# Spannungsteiler_low.net
KiCad netlist of a schematic drawn in Altium Designer
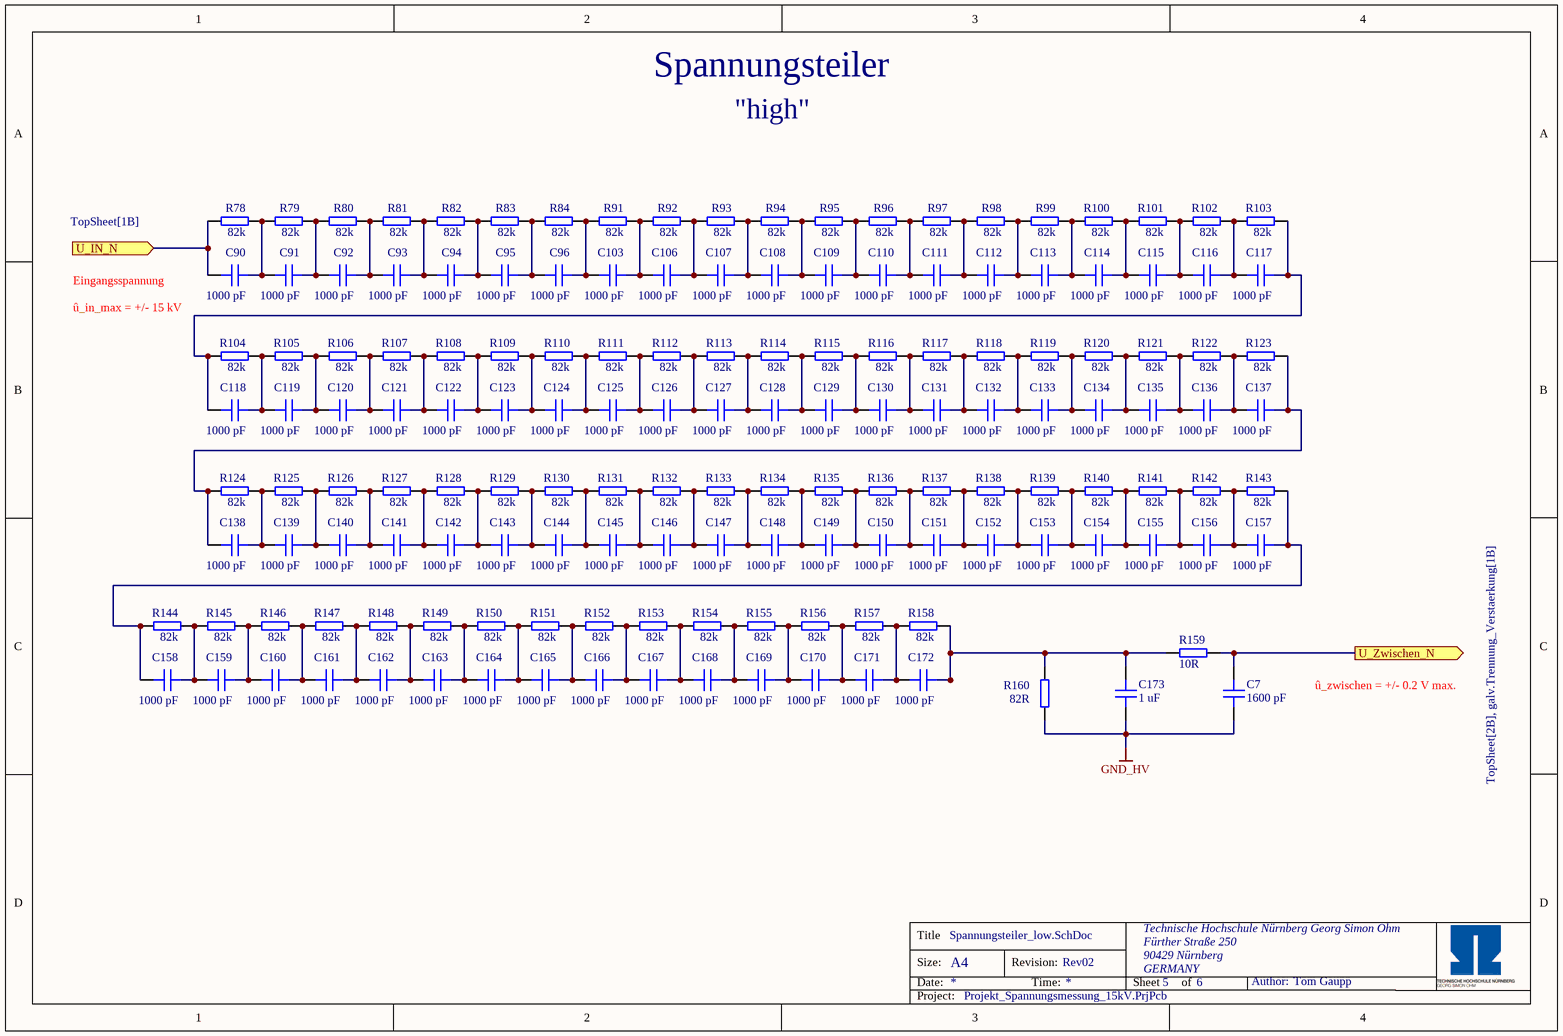
[diagram p0: Spannungsteiler_low.SchDoc]

(export (version "E")
  (design (tool "Eeschema 10.0.6"))
  (components
    (comp (ref "C7")
      (value "1600 pF")
      (footprint "C_1206")
      (description "Capacitor 1206, 25V, 1600pF, X8R, 10%")
      (fields
        (field (name "MANUFACTURER PART NUMBER") "C1206C162K3HACTU")
        (field (name "MANUFACTURER") "KEMET")
        (field (name "CREATED FROM") "TGaupp")
      )
      (libsource (lib "user") (part "Capacitor"))
    )
    (comp (ref "C90")
      (value "1000 pF")
      (footprint "C_1206")
      (description "Capacitor 1206, 200VDC, 1000pF, C0G, 5%")
      (fields
        (field (name "MANUFACTURER") "KEMET")
        (field (name "MANUFACTURER PART NUMBER") "C1206C102J2GACTU")
        (field (name "CREATED FROM") "TGaupp")
      )
      (libsource (lib "user") (part "Capacitor"))
    )
    (comp (ref "C91")
      (value "1000 pF")
      (footprint "C_1206")
      (description "Capacitor 1206, 200VDC, 1000pF, C0G, 5%")
      (fields
        (field (name "MANUFACTURER") "KEMET")
        (field (name "MANUFACTURER PART NUMBER") "C1206C102J2GACTU")
        (field (name "CREATED FROM") "TGaupp")
      )
      (libsource (lib "user") (part "Capacitor"))
    )
    (comp (ref "C92")
      (value "1000 pF")
      (footprint "C_1206")
      (description "Capacitor 1206, 200VDC, 1000pF, C0G, 5%")
      (fields
        (field (name "MANUFACTURER") "KEMET")
        (field (name "MANUFACTURER PART NUMBER") "C1206C102J2GACTU")
        (field (name "CREATED FROM") "TGaupp")
      )
      (libsource (lib "user") (part "Capacitor"))
    )
    (comp (ref "C93")
      (value "1000 pF")
      (footprint "C_1206")
      (description "Capacitor 1206, 200VDC, 1000pF, C0G, 5%")
      (fields
        (field (name "MANUFACTURER") "KEMET")
        (field (name "MANUFACTURER PART NUMBER") "C1206C102J2GACTU")
        (field (name "CREATED FROM") "TGaupp")
      )
      (libsource (lib "user") (part "Capacitor"))
    )
    (comp (ref "C94")
      (value "1000 pF")
      (footprint "C_1206")
      (description "Capacitor 1206, 200VDC, 1000pF, C0G, 5%")
      (fields
        (field (name "MANUFACTURER") "KEMET")
        (field (name "MANUFACTURER PART NUMBER") "C1206C102J2GACTU")
        (field (name "CREATED FROM") "TGaupp")
      )
      (libsource (lib "user") (part "Capacitor"))
    )
    (comp (ref "C95")
      (value "1000 pF")
      (footprint "C_1206")
      (description "Capacitor 1206, 200VDC, 1000pF, C0G, 5%")
      (fields
        (field (name "MANUFACTURER") "KEMET")
        (field (name "MANUFACTURER PART NUMBER") "C1206C102J2GACTU")
        (field (name "CREATED FROM") "TGaupp")
      )
      (libsource (lib "user") (part "Capacitor"))
    )
    (comp (ref "C96")
      (value "1000 pF")
      (footprint "C_1206")
      (description "Capacitor 1206, 200VDC, 1000pF, C0G, 5%")
      (fields
        (field (name "MANUFACTURER") "KEMET")
        (field (name "MANUFACTURER PART NUMBER") "C1206C102J2GACTU")
        (field (name "CREATED FROM") "TGaupp")
      )
      (libsource (lib "user") (part "Capacitor"))
    )
    (comp (ref "C103")
      (value "1000 pF")
      (footprint "C_1206")
      (description "Capacitor 1206, 200VDC, 1000pF, C0G, 5%")
      (fields
        (field (name "MANUFACTURER") "KEMET")
        (field (name "MANUFACTURER PART NUMBER") "C1206C102J2GACTU")
        (field (name "CREATED FROM") "TGaupp")
      )
      (libsource (lib "user") (part "Capacitor"))
    )
    (comp (ref "C106")
      (value "1000 pF")
      (footprint "C_1206")
      (description "Capacitor 1206, 200VDC, 1000pF, C0G, 5%")
      (fields
        (field (name "MANUFACTURER") "KEMET")
        (field (name "MANUFACTURER PART NUMBER") "C1206C102J2GACTU")
        (field (name "CREATED FROM") "TGaupp")
      )
      (libsource (lib "user") (part "Capacitor"))
    )
    (comp (ref "C107")
      (value "1000 pF")
      (footprint "C_1206")
      (description "Capacitor 1206, 200VDC, 1000pF, C0G, 5%")
      (fields
        (field (name "MANUFACTURER") "KEMET")
        (field (name "MANUFACTURER PART NUMBER") "C1206C102J2GACTU")
        (field (name "CREATED FROM") "TGaupp")
      )
      (libsource (lib "user") (part "Capacitor"))
    )
    (comp (ref "C108")
      (value "1000 pF")
      (footprint "C_1206")
      (description "Capacitor 1206, 200VDC, 1000pF, C0G, 5%")
      (fields
        (field (name "MANUFACTURER") "KEMET")
        (field (name "MANUFACTURER PART NUMBER") "C1206C102J2GACTU")
        (field (name "CREATED FROM") "TGaupp")
      )
      (libsource (lib "user") (part "Capacitor"))
    )
    (comp (ref "C109")
      (value "1000 pF")
      (footprint "C_1206")
      (description "Capacitor 1206, 200VDC, 1000pF, C0G, 5%")
      (fields
        (field (name "MANUFACTURER") "KEMET")
        (field (name "MANUFACTURER PART NUMBER") "C1206C102J2GACTU")
        (field (name "CREATED FROM") "TGaupp")
      )
      (libsource (lib "user") (part "Capacitor"))
    )
    (comp (ref "C110")
      (value "1000 pF")
      (footprint "C_1206")
      (description "Capacitor 1206, 200VDC, 1000pF, C0G, 5%")
      (fields
        (field (name "MANUFACTURER") "KEMET")
        (field (name "MANUFACTURER PART NUMBER") "C1206C102J2GACTU")
        (field (name "CREATED FROM") "TGaupp")
      )
      (libsource (lib "user") (part "Capacitor"))
    )
    (comp (ref "C111")
      (value "1000 pF")
      (footprint "C_1206")
      (description "Capacitor 1206, 200VDC, 1000pF, C0G, 5%")
      (fields
        (field (name "MANUFACTURER") "KEMET")
        (field (name "MANUFACTURER PART NUMBER") "C1206C102J2GACTU")
        (field (name "CREATED FROM") "TGaupp")
      )
      (libsource (lib "user") (part "Capacitor"))
    )
    (comp (ref "C112")
      (value "1000 pF")
      (footprint "C_1206")
      (description "Capacitor 1206, 200VDC, 1000pF, C0G, 5%")
      (fields
        (field (name "MANUFACTURER") "KEMET")
        (field (name "MANUFACTURER PART NUMBER") "C1206C102J2GACTU")
        (field (name "CREATED FROM") "TGaupp")
      )
      (libsource (lib "user") (part "Capacitor"))
    )
    (comp (ref "C113")
      (value "1000 pF")
      (footprint "C_1206")
      (description "Capacitor 1206, 200VDC, 1000pF, C0G, 5%")
      (fields
        (field (name "MANUFACTURER") "KEMET")
        (field (name "MANUFACTURER PART NUMBER") "C1206C102J2GACTU")
        (field (name "CREATED FROM") "TGaupp")
      )
      (libsource (lib "user") (part "Capacitor"))
    )
    (comp (ref "C114")
      (value "1000 pF")
      (footprint "C_1206")
      (description "Capacitor 1206, 200VDC, 1000pF, C0G, 5%")
      (fields
        (field (name "MANUFACTURER") "KEMET")
        (field (name "MANUFACTURER PART NUMBER") "C1206C102J2GACTU")
        (field (name "CREATED FROM") "TGaupp")
      )
      (libsource (lib "user") (part "Capacitor"))
    )
    (comp (ref "C115")
      (value "1000 pF")
      (footprint "C_1206")
      (description "Capacitor 1206, 200VDC, 1000pF, C0G, 5%")
      (fields
        (field (name "MANUFACTURER") "KEMET")
        (field (name "MANUFACTURER PART NUMBER") "C1206C102J2GACTU")
        (field (name "CREATED FROM") "TGaupp")
      )
      (libsource (lib "user") (part "Capacitor"))
    )
    (comp (ref "C116")
      (value "1000 pF")
      (footprint "C_1206")
      (description "Capacitor 1206, 200VDC, 1000pF, C0G, 5%")
      (fields
        (field (name "MANUFACTURER") "KEMET")
        (field (name "MANUFACTURER PART NUMBER") "C1206C102J2GACTU")
        (field (name "CREATED FROM") "TGaupp")
      )
      (libsource (lib "user") (part "Capacitor"))
    )
    (comp (ref "C117")
      (value "1000 pF")
      (footprint "C_1206")
      (description "Capacitor 1206, 200VDC, 1000pF, C0G, 5%")
      (fields
        (field (name "MANUFACTURER") "KEMET")
        (field (name "MANUFACTURER PART NUMBER") "C1206C102J2GACTU")
        (field (name "CREATED FROM") "TGaupp")
      )
      (libsource (lib "user") (part "Capacitor"))
    )
    (comp (ref "C118")
      (value "1000 pF")
      (footprint "C_1206")
      (description "Capacitor 1206, 200VDC, 1000pF, C0G, 5%")
      (fields
        (field (name "MANUFACTURER") "KEMET")
        (field (name "MANUFACTURER PART NUMBER") "C1206C102J2GACTU")
        (field (name "CREATED FROM") "TGaupp")
      )
      (libsource (lib "user") (part "Capacitor"))
    )
    (comp (ref "C119")
      (value "1000 pF")
      (footprint "C_1206")
      (description "Capacitor 1206, 200VDC, 1000pF, C0G, 5%")
      (fields
        (field (name "MANUFACTURER") "KEMET")
        (field (name "MANUFACTURER PART NUMBER") "C1206C102J2GACTU")
        (field (name "CREATED FROM") "TGaupp")
      )
      (libsource (lib "user") (part "Capacitor"))
    )
    (comp (ref "C120")
      (value "1000 pF")
      (footprint "C_1206")
      (description "Capacitor 1206, 200VDC, 1000pF, C0G, 5%")
      (fields
        (field (name "MANUFACTURER") "KEMET")
        (field (name "MANUFACTURER PART NUMBER") "C1206C102J2GACTU")
        (field (name "CREATED FROM") "TGaupp")
      )
      (libsource (lib "user") (part "Capacitor"))
    )
    (comp (ref "C121")
      (value "1000 pF")
      (footprint "C_1206")
      (description "Capacitor 1206, 200VDC, 1000pF, C0G, 5%")
      (fields
        (field (name "MANUFACTURER") "KEMET")
        (field (name "MANUFACTURER PART NUMBER") "C1206C102J2GACTU")
        (field (name "CREATED FROM") "TGaupp")
      )
      (libsource (lib "user") (part "Capacitor"))
    )
    (comp (ref "C122")
      (value "1000 pF")
      (footprint "C_1206")
      (description "Capacitor 1206, 200VDC, 1000pF, C0G, 5%")
      (fields
        (field (name "MANUFACTURER") "KEMET")
        (field (name "MANUFACTURER PART NUMBER") "C1206C102J2GACTU")
        (field (name "CREATED FROM") "TGaupp")
      )
      (libsource (lib "user") (part "Capacitor"))
    )
    (comp (ref "C123")
      (value "1000 pF")
      (footprint "C_1206")
      (description "Capacitor 1206, 200VDC, 1000pF, C0G, 5%")
      (fields
        (field (name "MANUFACTURER") "KEMET")
        (field (name "MANUFACTURER PART NUMBER") "C1206C102J2GACTU")
        (field (name "CREATED FROM") "TGaupp")
      )
      (libsource (lib "user") (part "Capacitor"))
    )
    (comp (ref "C124")
      (value "1000 pF")
      (footprint "C_1206")
      (description "Capacitor 1206, 200VDC, 1000pF, C0G, 5%")
      (fields
        (field (name "MANUFACTURER") "KEMET")
        (field (name "MANUFACTURER PART NUMBER") "C1206C102J2GACTU")
        (field (name "CREATED FROM") "TGaupp")
      )
      (libsource (lib "user") (part "Capacitor"))
    )
    (comp (ref "C125")
      (value "1000 pF")
      (footprint "C_1206")
      (description "Capacitor 1206, 200VDC, 1000pF, C0G, 5%")
      (fields
        (field (name "MANUFACTURER") "KEMET")
        (field (name "MANUFACTURER PART NUMBER") "C1206C102J2GACTU")
        (field (name "CREATED FROM") "TGaupp")
      )
      (libsource (lib "user") (part "Capacitor"))
    )
    (comp (ref "C126")
      (value "1000 pF")
      (footprint "C_1206")
      (description "Capacitor 1206, 200VDC, 1000pF, C0G, 5%")
      (fields
        (field (name "MANUFACTURER") "KEMET")
        (field (name "MANUFACTURER PART NUMBER") "C1206C102J2GACTU")
        (field (name "CREATED FROM") "TGaupp")
      )
      (libsource (lib "user") (part "Capacitor"))
    )
    (comp (ref "C127")
      (value "1000 pF")
      (footprint "C_1206")
      (description "Capacitor 1206, 200VDC, 1000pF, C0G, 5%")
      (fields
        (field (name "MANUFACTURER") "KEMET")
        (field (name "MANUFACTURER PART NUMBER") "C1206C102J2GACTU")
        (field (name "CREATED FROM") "TGaupp")
      )
      (libsource (lib "user") (part "Capacitor"))
    )
    (comp (ref "C128")
      (value "1000 pF")
      (footprint "C_1206")
      (description "Capacitor 1206, 200VDC, 1000pF, C0G, 5%")
      (fields
        (field (name "MANUFACTURER") "KEMET")
        (field (name "MANUFACTURER PART NUMBER") "C1206C102J2GACTU")
        (field (name "CREATED FROM") "TGaupp")
      )
      (libsource (lib "user") (part "Capacitor"))
    )
    (comp (ref "C129")
      (value "1000 pF")
      (footprint "C_1206")
      (description "Capacitor 1206, 200VDC, 1000pF, C0G, 5%")
      (fields
        (field (name "MANUFACTURER") "KEMET")
        (field (name "MANUFACTURER PART NUMBER") "C1206C102J2GACTU")
        (field (name "CREATED FROM") "TGaupp")
      )
      (libsource (lib "user") (part "Capacitor"))
    )
    (comp (ref "C130")
      (value "1000 pF")
      (footprint "C_1206")
      (description "Capacitor 1206, 200VDC, 1000pF, C0G, 5%")
      (fields
        (field (name "MANUFACTURER") "KEMET")
        (field (name "MANUFACTURER PART NUMBER") "C1206C102J2GACTU")
        (field (name "CREATED FROM") "TGaupp")
      )
      (libsource (lib "user") (part "Capacitor"))
    )
    (comp (ref "C131")
      (value "1000 pF")
      (footprint "C_1206")
      (description "Capacitor 1206, 200VDC, 1000pF, C0G, 5%")
      (fields
        (field (name "MANUFACTURER") "KEMET")
        (field (name "MANUFACTURER PART NUMBER") "C1206C102J2GACTU")
        (field (name "CREATED FROM") "TGaupp")
      )
      (libsource (lib "user") (part "Capacitor"))
    )
    (comp (ref "C132")
      (value "1000 pF")
      (footprint "C_1206")
      (description "Capacitor 1206, 200VDC, 1000pF, C0G, 5%")
      (fields
        (field (name "MANUFACTURER") "KEMET")
        (field (name "MANUFACTURER PART NUMBER") "C1206C102J2GACTU")
        (field (name "CREATED FROM") "TGaupp")
      )
      (libsource (lib "user") (part "Capacitor"))
    )
    (comp (ref "C133")
      (value "1000 pF")
      (footprint "C_1206")
      (description "Capacitor 1206, 200VDC, 1000pF, C0G, 5%")
      (fields
        (field (name "MANUFACTURER") "KEMET")
        (field (name "MANUFACTURER PART NUMBER") "C1206C102J2GACTU")
        (field (name "CREATED FROM") "TGaupp")
      )
      (libsource (lib "user") (part "Capacitor"))
    )
    (comp (ref "C134")
      (value "1000 pF")
      (footprint "C_1206")
      (description "Capacitor 1206, 200VDC, 1000pF, C0G, 5%")
      (fields
        (field (name "MANUFACTURER") "KEMET")
        (field (name "MANUFACTURER PART NUMBER") "C1206C102J2GACTU")
        (field (name "CREATED FROM") "TGaupp")
      )
      (libsource (lib "user") (part "Capacitor"))
    )
    (comp (ref "C135")
      (value "1000 pF")
      (footprint "C_1206")
      (description "Capacitor 1206, 200VDC, 1000pF, C0G, 5%")
      (fields
        (field (name "MANUFACTURER") "KEMET")
        (field (name "MANUFACTURER PART NUMBER") "C1206C102J2GACTU")
        (field (name "CREATED FROM") "TGaupp")
      )
      (libsource (lib "user") (part "Capacitor"))
    )
    (comp (ref "C136")
      (value "1000 pF")
      (footprint "C_1206")
      (description "Capacitor 1206, 200VDC, 1000pF, C0G, 5%")
      (fields
        (field (name "MANUFACTURER") "KEMET")
        (field (name "MANUFACTURER PART NUMBER") "C1206C102J2GACTU")
        (field (name "CREATED FROM") "TGaupp")
      )
      (libsource (lib "user") (part "Capacitor"))
    )
    (comp (ref "C137")
      (value "1000 pF")
      (footprint "C_1206")
      (description "Capacitor 1206, 200VDC, 1000pF, C0G, 5%")
      (fields
        (field (name "MANUFACTURER") "KEMET")
        (field (name "MANUFACTURER PART NUMBER") "C1206C102J2GACTU")
        (field (name "CREATED FROM") "TGaupp")
      )
      (libsource (lib "user") (part "Capacitor"))
    )
    (comp (ref "C138")
      (value "1000 pF")
      (footprint "C_1206")
      (description "Capacitor 1206, 200VDC, 1000pF, C0G, 5%")
      (fields
        (field (name "MANUFACTURER") "KEMET")
        (field (name "MANUFACTURER PART NUMBER") "C1206C102J2GACTU")
        (field (name "CREATED FROM") "TGaupp")
      )
      (libsource (lib "user") (part "Capacitor"))
    )
    (comp (ref "C139")
      (value "1000 pF")
      (footprint "C_1206")
      (description "Capacitor 1206, 200VDC, 1000pF, C0G, 5%")
      (fields
        (field (name "MANUFACTURER") "KEMET")
        (field (name "MANUFACTURER PART NUMBER") "C1206C102J2GACTU")
        (field (name "CREATED FROM") "TGaupp")
      )
      (libsource (lib "user") (part "Capacitor"))
    )
    (comp (ref "C140")
      (value "1000 pF")
      (footprint "C_1206")
      (description "Capacitor 1206, 200VDC, 1000pF, C0G, 5%")
      (fields
        (field (name "MANUFACTURER") "KEMET")
        (field (name "MANUFACTURER PART NUMBER") "C1206C102J2GACTU")
        (field (name "CREATED FROM") "TGaupp")
      )
      (libsource (lib "user") (part "Capacitor"))
    )
    (comp (ref "C141")
      (value "1000 pF")
      (footprint "C_1206")
      (description "Capacitor 1206, 200VDC, 1000pF, C0G, 5%")
      (fields
        (field (name "MANUFACTURER") "KEMET")
        (field (name "MANUFACTURER PART NUMBER") "C1206C102J2GACTU")
        (field (name "CREATED FROM") "TGaupp")
      )
      (libsource (lib "user") (part "Capacitor"))
    )
    (comp (ref "C142")
      (value "1000 pF")
      (footprint "C_1206")
      (description "Capacitor 1206, 200VDC, 1000pF, C0G, 5%")
      (fields
        (field (name "MANUFACTURER") "KEMET")
        (field (name "MANUFACTURER PART NUMBER") "C1206C102J2GACTU")
        (field (name "CREATED FROM") "TGaupp")
      )
      (libsource (lib "user") (part "Capacitor"))
    )
    (comp (ref "C143")
      (value "1000 pF")
      (footprint "C_1206")
      (description "Capacitor 1206, 200VDC, 1000pF, C0G, 5%")
      (fields
        (field (name "MANUFACTURER") "KEMET")
        (field (name "MANUFACTURER PART NUMBER") "C1206C102J2GACTU")
        (field (name "CREATED FROM") "TGaupp")
      )
      (libsource (lib "user") (part "Capacitor"))
    )
    (comp (ref "C144")
      (value "1000 pF")
      (footprint "C_1206")
      (description "Capacitor 1206, 200VDC, 1000pF, C0G, 5%")
      (fields
        (field (name "MANUFACTURER") "KEMET")
        (field (name "MANUFACTURER PART NUMBER") "C1206C102J2GACTU")
        (field (name "CREATED FROM") "TGaupp")
      )
      (libsource (lib "user") (part "Capacitor"))
    )
    (comp (ref "C145")
      (value "1000 pF")
      (footprint "C_1206")
      (description "Capacitor 1206, 200VDC, 1000pF, C0G, 5%")
      (fields
        (field (name "MANUFACTURER") "KEMET")
        (field (name "MANUFACTURER PART NUMBER") "C1206C102J2GACTU")
        (field (name "CREATED FROM") "TGaupp")
      )
      (libsource (lib "user") (part "Capacitor"))
    )
    (comp (ref "C146")
      (value "1000 pF")
      (footprint "C_1206")
      (description "Capacitor 1206, 200VDC, 1000pF, C0G, 5%")
      (fields
        (field (name "MANUFACTURER") "KEMET")
        (field (name "MANUFACTURER PART NUMBER") "C1206C102J2GACTU")
        (field (name "CREATED FROM") "TGaupp")
      )
      (libsource (lib "user") (part "Capacitor"))
    )
    (comp (ref "C147")
      (value "1000 pF")
      (footprint "C_1206")
      (description "Capacitor 1206, 200VDC, 1000pF, C0G, 5%")
      (fields
        (field (name "MANUFACTURER") "KEMET")
        (field (name "MANUFACTURER PART NUMBER") "C1206C102J2GACTU")
        (field (name "CREATED FROM") "TGaupp")
      )
      (libsource (lib "user") (part "Capacitor"))
    )
    (comp (ref "C148")
      (value "1000 pF")
      (footprint "C_1206")
      (description "Capacitor 1206, 200VDC, 1000pF, C0G, 5%")
      (fields
        (field (name "MANUFACTURER") "KEMET")
        (field (name "MANUFACTURER PART NUMBER") "C1206C102J2GACTU")
        (field (name "CREATED FROM") "TGaupp")
      )
      (libsource (lib "user") (part "Capacitor"))
    )
    (comp (ref "C149")
      (value "1000 pF")
      (footprint "C_1206")
      (description "Capacitor 1206, 200VDC, 1000pF, C0G, 5%")
      (fields
        (field (name "MANUFACTURER") "KEMET")
        (field (name "MANUFACTURER PART NUMBER") "C1206C102J2GACTU")
        (field (name "CREATED FROM") "TGaupp")
      )
      (libsource (lib "user") (part "Capacitor"))
    )
    (comp (ref "C150")
      (value "1000 pF")
      (footprint "C_1206")
      (description "Capacitor 1206, 200VDC, 1000pF, C0G, 5%")
      (fields
        (field (name "MANUFACTURER") "KEMET")
        (field (name "MANUFACTURER PART NUMBER") "C1206C102J2GACTU")
        (field (name "CREATED FROM") "TGaupp")
      )
      (libsource (lib "user") (part "Capacitor"))
    )
    (comp (ref "C151")
      (value "1000 pF")
      (footprint "C_1206")
      (description "Capacitor 1206, 200VDC, 1000pF, C0G, 5%")
      (fields
        (field (name "MANUFACTURER") "KEMET")
        (field (name "MANUFACTURER PART NUMBER") "C1206C102J2GACTU")
        (field (name "CREATED FROM") "TGaupp")
      )
      (libsource (lib "user") (part "Capacitor"))
    )
    (comp (ref "C152")
      (value "1000 pF")
      (footprint "C_1206")
      (description "Capacitor 1206, 200VDC, 1000pF, C0G, 5%")
      (fields
        (field (name "MANUFACTURER") "KEMET")
        (field (name "MANUFACTURER PART NUMBER") "C1206C102J2GACTU")
        (field (name "CREATED FROM") "TGaupp")
      )
      (libsource (lib "user") (part "Capacitor"))
    )
    (comp (ref "C153")
      (value "1000 pF")
      (footprint "C_1206")
      (description "Capacitor 1206, 200VDC, 1000pF, C0G, 5%")
      (fields
        (field (name "MANUFACTURER") "KEMET")
        (field (name "MANUFACTURER PART NUMBER") "C1206C102J2GACTU")
        (field (name "CREATED FROM") "TGaupp")
      )
      (libsource (lib "user") (part "Capacitor"))
    )
    (comp (ref "C154")
      (value "1000 pF")
      (footprint "C_1206")
      (description "Capacitor 1206, 200VDC, 1000pF, C0G, 5%")
      (fields
        (field (name "MANUFACTURER") "KEMET")
        (field (name "MANUFACTURER PART NUMBER") "C1206C102J2GACTU")
        (field (name "CREATED FROM") "TGaupp")
      )
      (libsource (lib "user") (part "Capacitor"))
    )
    (comp (ref "C155")
      (value "1000 pF")
      (footprint "C_1206")
      (description "Capacitor 1206, 200VDC, 1000pF, C0G, 5%")
      (fields
        (field (name "MANUFACTURER") "KEMET")
        (field (name "MANUFACTURER PART NUMBER") "C1206C102J2GACTU")
        (field (name "CREATED FROM") "TGaupp")
      )
      (libsource (lib "user") (part "Capacitor"))
    )
    (comp (ref "C156")
      (value "1000 pF")
      (footprint "C_1206")
      (description "Capacitor 1206, 200VDC, 1000pF, C0G, 5%")
      (fields
        (field (name "MANUFACTURER") "KEMET")
        (field (name "MANUFACTURER PART NUMBER") "C1206C102J2GACTU")
        (field (name "CREATED FROM") "TGaupp")
      )
      (libsource (lib "user") (part "Capacitor"))
    )
    (comp (ref "C157")
      (value "1000 pF")
      (footprint "C_1206")
      (description "Capacitor 1206, 200VDC, 1000pF, C0G, 5%")
      (fields
        (field (name "MANUFACTURER") "KEMET")
        (field (name "MANUFACTURER PART NUMBER") "C1206C102J2GACTU")
        (field (name "CREATED FROM") "TGaupp")
      )
      (libsource (lib "user") (part "Capacitor"))
    )
    (comp (ref "C158")
      (value "1000 pF")
      (footprint "C_1206")
      (description "Capacitor 1206, 200VDC, 1000pF, C0G, 5%")
      (fields
        (field (name "MANUFACTURER") "KEMET")
        (field (name "MANUFACTURER PART NUMBER") "C1206C102J2GACTU")
        (field (name "CREATED FROM") "TGaupp")
      )
      (libsource (lib "user") (part "Capacitor"))
    )
    (comp (ref "C159")
      (value "1000 pF")
      (footprint "C_1206")
      (description "Capacitor 1206, 200VDC, 1000pF, C0G, 5%")
      (fields
        (field (name "MANUFACTURER") "KEMET")
        (field (name "MANUFACTURER PART NUMBER") "C1206C102J2GACTU")
        (field (name "CREATED FROM") "TGaupp")
      )
      (libsource (lib "user") (part "Capacitor"))
    )
    (comp (ref "C160")
      (value "1000 pF")
      (footprint "C_1206")
      (description "Capacitor 1206, 200VDC, 1000pF, C0G, 5%")
      (fields
        (field (name "MANUFACTURER") "KEMET")
        (field (name "MANUFACTURER PART NUMBER") "C1206C102J2GACTU")
        (field (name "CREATED FROM") "TGaupp")
      )
      (libsource (lib "user") (part "Capacitor"))
    )
    (comp (ref "C161")
      (value "1000 pF")
      (footprint "C_1206")
      (description "Capacitor 1206, 200VDC, 1000pF, C0G, 5%")
      (fields
        (field (name "MANUFACTURER") "KEMET")
        (field (name "MANUFACTURER PART NUMBER") "C1206C102J2GACTU")
        (field (name "CREATED FROM") "TGaupp")
      )
      (libsource (lib "user") (part "Capacitor"))
    )
    (comp (ref "C162")
      (value "1000 pF")
      (footprint "C_1206")
      (description "Capacitor 1206, 200VDC, 1000pF, C0G, 5%")
      (fields
        (field (name "MANUFACTURER") "KEMET")
        (field (name "MANUFACTURER PART NUMBER") "C1206C102J2GACTU")
        (field (name "CREATED FROM") "TGaupp")
      )
      (libsource (lib "user") (part "Capacitor"))
    )
    (comp (ref "C163")
      (value "1000 pF")
      (footprint "C_1206")
      (description "Capacitor 1206, 200VDC, 1000pF, C0G, 5%")
      (fields
        (field (name "MANUFACTURER") "KEMET")
        (field (name "MANUFACTURER PART NUMBER") "C1206C102J2GACTU")
        (field (name "CREATED FROM") "TGaupp")
      )
      (libsource (lib "user") (part "Capacitor"))
    )
    (comp (ref "C164")
      (value "1000 pF")
      (footprint "C_1206")
      (description "Capacitor 1206, 200VDC, 1000pF, C0G, 5%")
      (fields
        (field (name "MANUFACTURER") "KEMET")
        (field (name "MANUFACTURER PART NUMBER") "C1206C102J2GACTU")
        (field (name "CREATED FROM") "TGaupp")
      )
      (libsource (lib "user") (part "Capacitor"))
    )
    (comp (ref "C165")
      (value "1000 pF")
      (footprint "C_1206")
      (description "Capacitor 1206, 200VDC, 1000pF, C0G, 5%")
      (fields
        (field (name "MANUFACTURER") "KEMET")
        (field (name "MANUFACTURER PART NUMBER") "C1206C102J2GACTU")
        (field (name "CREATED FROM") "TGaupp")
      )
      (libsource (lib "user") (part "Capacitor"))
    )
    (comp (ref "C166")
      (value "1000 pF")
      (footprint "C_1206")
      (description "Capacitor 1206, 200VDC, 1000pF, C0G, 5%")
      (fields
        (field (name "MANUFACTURER") "KEMET")
        (field (name "MANUFACTURER PART NUMBER") "C1206C102J2GACTU")
        (field (name "CREATED FROM") "TGaupp")
      )
      (libsource (lib "user") (part "Capacitor"))
    )
    (comp (ref "C167")
      (value "1000 pF")
      (footprint "C_1206")
      (description "Capacitor 1206, 200VDC, 1000pF, C0G, 5%")
      (fields
        (field (name "MANUFACTURER") "KEMET")
        (field (name "MANUFACTURER PART NUMBER") "C1206C102J2GACTU")
        (field (name "CREATED FROM") "TGaupp")
      )
      (libsource (lib "user") (part "Capacitor"))
    )
    (comp (ref "C168")
      (value "1000 pF")
      (footprint "C_1206")
      (description "Capacitor 1206, 200VDC, 1000pF, C0G, 5%")
      (fields
        (field (name "MANUFACTURER") "KEMET")
        (field (name "MANUFACTURER PART NUMBER") "C1206C102J2GACTU")
        (field (name "CREATED FROM") "TGaupp")
      )
      (libsource (lib "user") (part "Capacitor"))
    )
    (comp (ref "C169")
      (value "1000 pF")
      (footprint "C_1206")
      (description "Capacitor 1206, 200VDC, 1000pF, C0G, 5%")
      (fields
        (field (name "MANUFACTURER") "KEMET")
        (field (name "MANUFACTURER PART NUMBER") "C1206C102J2GACTU")
        (field (name "CREATED FROM") "TGaupp")
      )
      (libsource (lib "user") (part "Capacitor"))
    )
    (comp (ref "C170")
      (value "1000 pF")
      (footprint "C_1206")
      (description "Capacitor 1206, 200VDC, 1000pF, C0G, 5%")
      (fields
        (field (name "MANUFACTURER") "KEMET")
        (field (name "MANUFACTURER PART NUMBER") "C1206C102J2GACTU")
        (field (name "CREATED FROM") "TGaupp")
      )
      (libsource (lib "user") (part "Capacitor"))
    )
    (comp (ref "C171")
      (value "1000 pF")
      (footprint "C_1206")
      (description "Capacitor 1206, 200VDC, 1000pF, C0G, 5%")
      (fields
        (field (name "MANUFACTURER") "KEMET")
        (field (name "MANUFACTURER PART NUMBER") "C1206C102J2GACTU")
        (field (name "CREATED FROM") "TGaupp")
      )
      (libsource (lib "user") (part "Capacitor"))
    )
    (comp (ref "C172")
      (value "1000 pF")
      (footprint "C_1206")
      (description "Capacitor 1206, 200VDC, 1000pF, C0G, 5%")
      (fields
        (field (name "MANUFACTURER") "KEMET")
        (field (name "MANUFACTURER PART NUMBER") "C1206C102J2GACTU")
        (field (name "CREATED FROM") "TGaupp")
      )
      (libsource (lib "user") (part "Capacitor"))
    )
    (comp (ref "C173")
      (value "1 uF")
      (footprint "C_1206")
      (description "Capacitor 1206, 50V, 1uF, X7R, 5%")
      (fields
        (field (name "MANUFACTURER PART NUMBER") "C1206X105J5RACTU")
        (field (name "MANUFACTURER") "KEMET")
        (field (name "CREATED FROM") "TGaupp")
      )
      (libsource (lib "user") (part "Capacitor"))
    )
    (comp (ref "R78")
      (value "82k")
      (footprint "RES 1206_3216")
      (description "SMD resistor 82Kohms .1% 25ppm")
      (fields
        (field (name "MANUFACTURER") "Vishay")
        (field (name "MANUFACTURER PART NUMBER") "TNPW120682K0BEEA")
        (field (name "CREATED FROM") "TGaupp")
      )
      (libsource (lib "user") (part "Resistor"))
    )
    (comp (ref "R79")
      (value "82k")
      (footprint "RES 1206_3216")
      (description "SMD resistor 82Kohms .1% 25ppm")
      (fields
        (field (name "MANUFACTURER") "Vishay")
        (field (name "MANUFACTURER PART NUMBER") "TNPW120682K0BEEA")
        (field (name "CREATED FROM") "TGaupp")
      )
      (libsource (lib "user") (part "Resistor"))
    )
    (comp (ref "R80")
      (value "82k")
      (footprint "RES 1206_3216")
      (description "SMD resistor 82Kohms .1% 25ppm")
      (fields
        (field (name "MANUFACTURER") "Vishay")
        (field (name "MANUFACTURER PART NUMBER") "TNPW120682K0BEEA")
        (field (name "CREATED FROM") "TGaupp")
      )
      (libsource (lib "user") (part "Resistor"))
    )
    (comp (ref "R81")
      (value "82k")
      (footprint "RES 1206_3216")
      (description "SMD resistor 82Kohms .1% 25ppm")
      (fields
        (field (name "MANUFACTURER") "Vishay")
        (field (name "MANUFACTURER PART NUMBER") "TNPW120682K0BEEA")
        (field (name "CREATED FROM") "TGaupp")
      )
      (libsource (lib "user") (part "Resistor"))
    )
    (comp (ref "R82")
      (value "82k")
      (footprint "RES 1206_3216")
      (description "SMD resistor 82Kohms .1% 25ppm")
      (fields
        (field (name "MANUFACTURER") "Vishay")
        (field (name "MANUFACTURER PART NUMBER") "TNPW120682K0BEEA")
        (field (name "CREATED FROM") "TGaupp")
      )
      (libsource (lib "user") (part "Resistor"))
    )
    (comp (ref "R83")
      (value "82k")
      (footprint "RES 1206_3216")
      (description "SMD resistor 82Kohms .1% 25ppm")
      (fields
        (field (name "MANUFACTURER") "Vishay")
        (field (name "MANUFACTURER PART NUMBER") "TNPW120682K0BEEA")
        (field (name "CREATED FROM") "TGaupp")
      )
      (libsource (lib "user") (part "Resistor"))
    )
    (comp (ref "R84")
      (value "82k")
      (footprint "RES 1206_3216")
      (description "SMD resistor 82Kohms .1% 25ppm")
      (fields
        (field (name "MANUFACTURER") "Vishay")
        (field (name "MANUFACTURER PART NUMBER") "TNPW120682K0BEEA")
        (field (name "CREATED FROM") "TGaupp")
      )
      (libsource (lib "user") (part "Resistor"))
    )
    (comp (ref "R91")
      (value "82k")
      (footprint "RES 1206_3216")
      (description "SMD resistor 82Kohms .1% 25ppm")
      (fields
        (field (name "MANUFACTURER") "Vishay")
        (field (name "MANUFACTURER PART NUMBER") "TNPW120682K0BEEA")
        (field (name "CREATED FROM") "TGaupp")
      )
      (libsource (lib "user") (part "Resistor"))
    )
    (comp (ref "R92")
      (value "82k")
      (footprint "RES 1206_3216")
      (description "SMD resistor 82Kohms .1% 25ppm")
      (fields
        (field (name "MANUFACTURER") "Vishay")
        (field (name "MANUFACTURER PART NUMBER") "TNPW120682K0BEEA")
        (field (name "CREATED FROM") "TGaupp")
      )
      (libsource (lib "user") (part "Resistor"))
    )
    (comp (ref "R93")
      (value "82k")
      (footprint "RES 1206_3216")
      (description "SMD resistor 82Kohms .1% 25ppm")
      (fields
        (field (name "MANUFACTURER") "Vishay")
        (field (name "MANUFACTURER PART NUMBER") "TNPW120682K0BEEA")
        (field (name "CREATED FROM") "TGaupp")
      )
      (libsource (lib "user") (part "Resistor"))
    )
    (comp (ref "R94")
      (value "82k")
      (footprint "RES 1206_3216")
      (description "SMD resistor 82Kohms .1% 25ppm")
      (fields
        (field (name "MANUFACTURER") "Vishay")
        (field (name "MANUFACTURER PART NUMBER") "TNPW120682K0BEEA")
        (field (name "CREATED FROM") "TGaupp")
      )
      (libsource (lib "user") (part "Resistor"))
    )
    (comp (ref "R95")
      (value "82k")
      (footprint "RES 1206_3216")
      (description "SMD resistor 82Kohms .1% 25ppm")
      (fields
        (field (name "MANUFACTURER") "Vishay")
        (field (name "MANUFACTURER PART NUMBER") "TNPW120682K0BEEA")
        (field (name "CREATED FROM") "TGaupp")
      )
      (libsource (lib "user") (part "Resistor"))
    )
    (comp (ref "R96")
      (value "82k")
      (footprint "RES 1206_3216")
      (description "SMD resistor 82Kohms .1% 25ppm")
      (fields
        (field (name "MANUFACTURER") "Vishay")
        (field (name "MANUFACTURER PART NUMBER") "TNPW120682K0BEEA")
        (field (name "CREATED FROM") "TGaupp")
      )
      (libsource (lib "user") (part "Resistor"))
    )
    (comp (ref "R97")
      (value "82k")
      (footprint "RES 1206_3216")
      (description "SMD resistor 82Kohms .1% 25ppm")
      (fields
        (field (name "MANUFACTURER") "Vishay")
        (field (name "MANUFACTURER PART NUMBER") "TNPW120682K0BEEA")
        (field (name "CREATED FROM") "TGaupp")
      )
      (libsource (lib "user") (part "Resistor"))
    )
    (comp (ref "R98")
      (value "82k")
      (footprint "RES 1206_3216")
      (description "SMD resistor 82Kohms .1% 25ppm")
      (fields
        (field (name "MANUFACTURER") "Vishay")
        (field (name "MANUFACTURER PART NUMBER") "TNPW120682K0BEEA")
        (field (name "CREATED FROM") "TGaupp")
      )
      (libsource (lib "user") (part "Resistor"))
    )
    (comp (ref "R99")
      (value "82k")
      (footprint "RES 1206_3216")
      (description "SMD resistor 82Kohms .1% 25ppm")
      (fields
        (field (name "MANUFACTURER") "Vishay")
        (field (name "MANUFACTURER PART NUMBER") "TNPW120682K0BEEA")
        (field (name "CREATED FROM") "TGaupp")
      )
      (libsource (lib "user") (part "Resistor"))
    )
    (comp (ref "R100")
      (value "82k")
      (footprint "RES 1206_3216")
      (description "SMD resistor 82Kohms .1% 25ppm")
      (fields
        (field (name "MANUFACTURER") "Vishay")
        (field (name "MANUFACTURER PART NUMBER") "TNPW120682K0BEEA")
        (field (name "CREATED FROM") "TGaupp")
      )
      (libsource (lib "user") (part "Resistor"))
    )
    (comp (ref "R101")
      (value "82k")
      (footprint "RES 1206_3216")
      (description "SMD resistor 82Kohms .1% 25ppm")
      (fields
        (field (name "MANUFACTURER") "Vishay")
        (field (name "MANUFACTURER PART NUMBER") "TNPW120682K0BEEA")
        (field (name "CREATED FROM") "TGaupp")
      )
      (libsource (lib "user") (part "Resistor"))
    )
    (comp (ref "R102")
      (value "82k")
      (footprint "RES 1206_3216")
      (description "SMD resistor 82Kohms .1% 25ppm")
      (fields
        (field (name "MANUFACTURER") "Vishay")
        (field (name "MANUFACTURER PART NUMBER") "TNPW120682K0BEEA")
        (field (name "CREATED FROM") "TGaupp")
      )
      (libsource (lib "user") (part "Resistor"))
    )
    (comp (ref "R103")
      (value "82k")
      (footprint "RES 1206_3216")
      (description "SMD resistor 82Kohms .1% 25ppm")
      (fields
        (field (name "MANUFACTURER") "Vishay")
        (field (name "MANUFACTURER PART NUMBER") "TNPW120682K0BEEA")
        (field (name "CREATED FROM") "TGaupp")
      )
      (libsource (lib "user") (part "Resistor"))
    )
    (comp (ref "R104")
      (value "82k")
      (footprint "RES 1206_3216")
      (description "SMD resistor 82Kohms .1% 25ppm")
      (fields
        (field (name "MANUFACTURER") "Vishay")
        (field (name "MANUFACTURER PART NUMBER") "TNPW120682K0BEEA")
        (field (name "CREATED FROM") "TGaupp")
      )
      (libsource (lib "user") (part "Resistor"))
    )
    (comp (ref "R105")
      (value "82k")
      (footprint "RES 1206_3216")
      (description "SMD resistor 82Kohms .1% 25ppm")
      (fields
        (field (name "MANUFACTURER") "Vishay")
        (field (name "MANUFACTURER PART NUMBER") "TNPW120682K0BEEA")
        (field (name "CREATED FROM") "TGaupp")
      )
      (libsource (lib "user") (part "Resistor"))
    )
    (comp (ref "R106")
      (value "82k")
      (footprint "RES 1206_3216")
      (description "SMD resistor 82Kohms .1% 25ppm")
      (fields
        (field (name "MANUFACTURER") "Vishay")
        (field (name "MANUFACTURER PART NUMBER") "TNPW120682K0BEEA")
        (field (name "CREATED FROM") "TGaupp")
      )
      (libsource (lib "user") (part "Resistor"))
    )
    (comp (ref "R107")
      (value "82k")
      (footprint "RES 1206_3216")
      (description "SMD resistor 82Kohms .1% 25ppm")
      (fields
        (field (name "MANUFACTURER") "Vishay")
        (field (name "MANUFACTURER PART NUMBER") "TNPW120682K0BEEA")
        (field (name "CREATED FROM") "TGaupp")
      )
      (libsource (lib "user") (part "Resistor"))
    )
    (comp (ref "R108")
      (value "82k")
      (footprint "RES 1206_3216")
      (description "SMD resistor 82Kohms .1% 25ppm")
      (fields
        (field (name "MANUFACTURER") "Vishay")
        (field (name "MANUFACTURER PART NUMBER") "TNPW120682K0BEEA")
        (field (name "CREATED FROM") "TGaupp")
      )
      (libsource (lib "user") (part "Resistor"))
    )
    (comp (ref "R109")
      (value "82k")
      (footprint "RES 1206_3216")
      (description "SMD resistor 82Kohms .1% 25ppm")
      (fields
        (field (name "MANUFACTURER") "Vishay")
        (field (name "MANUFACTURER PART NUMBER") "TNPW120682K0BEEA")
        (field (name "CREATED FROM") "TGaupp")
      )
      (libsource (lib "user") (part "Resistor"))
    )
    (comp (ref "R110")
      (value "82k")
      (footprint "RES 1206_3216")
      (description "SMD resistor 82Kohms .1% 25ppm")
      (fields
        (field (name "MANUFACTURER") "Vishay")
        (field (name "MANUFACTURER PART NUMBER") "TNPW120682K0BEEA")
        (field (name "CREATED FROM") "TGaupp")
      )
      (libsource (lib "user") (part "Resistor"))
    )
    (comp (ref "R111")
      (value "82k")
      (footprint "RES 1206_3216")
      (description "SMD resistor 82Kohms .1% 25ppm")
      (fields
        (field (name "MANUFACTURER") "Vishay")
        (field (name "MANUFACTURER PART NUMBER") "TNPW120682K0BEEA")
        (field (name "CREATED FROM") "TGaupp")
      )
      (libsource (lib "user") (part "Resistor"))
    )
    (comp (ref "R112")
      (value "82k")
      (footprint "RES 1206_3216")
      (description "SMD resistor 82Kohms .1% 25ppm")
      (fields
        (field (name "MANUFACTURER") "Vishay")
        (field (name "MANUFACTURER PART NUMBER") "TNPW120682K0BEEA")
        (field (name "CREATED FROM") "TGaupp")
      )
      (libsource (lib "user") (part "Resistor"))
    )
    (comp (ref "R113")
      (value "82k")
      (footprint "RES 1206_3216")
      (description "SMD resistor 82Kohms .1% 25ppm")
      (fields
        (field (name "MANUFACTURER") "Vishay")
        (field (name "MANUFACTURER PART NUMBER") "TNPW120682K0BEEA")
        (field (name "CREATED FROM") "TGaupp")
      )
      (libsource (lib "user") (part "Resistor"))
    )
    (comp (ref "R114")
      (value "82k")
      (footprint "RES 1206_3216")
      (description "SMD resistor 82Kohms .1% 25ppm")
      (fields
        (field (name "MANUFACTURER") "Vishay")
        (field (name "MANUFACTURER PART NUMBER") "TNPW120682K0BEEA")
        (field (name "CREATED FROM") "TGaupp")
      )
      (libsource (lib "user") (part "Resistor"))
    )
    (comp (ref "R115")
      (value "82k")
      (footprint "RES 1206_3216")
      (description "SMD resistor 82Kohms .1% 25ppm")
      (fields
        (field (name "MANUFACTURER") "Vishay")
        (field (name "MANUFACTURER PART NUMBER") "TNPW120682K0BEEA")
        (field (name "CREATED FROM") "TGaupp")
      )
      (libsource (lib "user") (part "Resistor"))
    )
    (comp (ref "R116")
      (value "82k")
      (footprint "RES 1206_3216")
      (description "SMD resistor 82Kohms .1% 25ppm")
      (fields
        (field (name "MANUFACTURER") "Vishay")
        (field (name "MANUFACTURER PART NUMBER") "TNPW120682K0BEEA")
        (field (name "CREATED FROM") "TGaupp")
      )
      (libsource (lib "user") (part "Resistor"))
    )
    (comp (ref "R117")
      (value "82k")
      (footprint "RES 1206_3216")
      (description "SMD resistor 82Kohms .1% 25ppm")
      (fields
        (field (name "MANUFACTURER") "Vishay")
        (field (name "MANUFACTURER PART NUMBER") "TNPW120682K0BEEA")
        (field (name "CREATED FROM") "TGaupp")
      )
      (libsource (lib "user") (part "Resistor"))
    )
    (comp (ref "R118")
      (value "82k")
      (footprint "RES 1206_3216")
      (description "SMD resistor 82Kohms .1% 25ppm")
      (fields
        (field (name "MANUFACTURER") "Vishay")
        (field (name "MANUFACTURER PART NUMBER") "TNPW120682K0BEEA")
        (field (name "CREATED FROM") "TGaupp")
      )
      (libsource (lib "user") (part "Resistor"))
    )
    (comp (ref "R119")
      (value "82k")
      (footprint "RES 1206_3216")
      (description "SMD resistor 82Kohms .1% 25ppm")
      (fields
        (field (name "MANUFACTURER") "Vishay")
        (field (name "MANUFACTURER PART NUMBER") "TNPW120682K0BEEA")
        (field (name "CREATED FROM") "TGaupp")
      )
      (libsource (lib "user") (part "Resistor"))
    )
    (comp (ref "R120")
      (value "82k")
      (footprint "RES 1206_3216")
      (description "SMD resistor 82Kohms .1% 25ppm")
      (fields
        (field (name "MANUFACTURER") "Vishay")
        (field (name "MANUFACTURER PART NUMBER") "TNPW120682K0BEEA")
        (field (name "CREATED FROM") "TGaupp")
      )
      (libsource (lib "user") (part "Resistor"))
    )
    (comp (ref "R121")
      (value "82k")
      (footprint "RES 1206_3216")
      (description "SMD resistor 82Kohms .1% 25ppm")
      (fields
        (field (name "MANUFACTURER") "Vishay")
        (field (name "MANUFACTURER PART NUMBER") "TNPW120682K0BEEA")
        (field (name "CREATED FROM") "TGaupp")
      )
      (libsource (lib "user") (part "Resistor"))
    )
    (comp (ref "R122")
      (value "82k")
      (footprint "RES 1206_3216")
      (description "SMD resistor 82Kohms .1% 25ppm")
      (fields
        (field (name "MANUFACTURER") "Vishay")
        (field (name "MANUFACTURER PART NUMBER") "TNPW120682K0BEEA")
        (field (name "CREATED FROM") "TGaupp")
      )
      (libsource (lib "user") (part "Resistor"))
    )
    (comp (ref "R123")
      (value "82k")
      (footprint "RES 1206_3216")
      (description "SMD resistor 82Kohms .1% 25ppm")
      (fields
        (field (name "MANUFACTURER") "Vishay")
        (field (name "MANUFACTURER PART NUMBER") "TNPW120682K0BEEA")
        (field (name "CREATED FROM") "TGaupp")
      )
      (libsource (lib "user") (part "Resistor"))
    )
    (comp (ref "R124")
      (value "82k")
      (footprint "RES 1206_3216")
      (description "SMD resistor 82Kohms .1% 25ppm")
      (fields
        (field (name "MANUFACTURER") "Vishay")
        (field (name "MANUFACTURER PART NUMBER") "TNPW120682K0BEEA")
        (field (name "CREATED FROM") "TGaupp")
      )
      (libsource (lib "user") (part "Resistor"))
    )
    (comp (ref "R125")
      (value "82k")
      (footprint "RES 1206_3216")
      (description "SMD resistor 82Kohms .1% 25ppm")
      (fields
        (field (name "MANUFACTURER") "Vishay")
        (field (name "MANUFACTURER PART NUMBER") "TNPW120682K0BEEA")
        (field (name "CREATED FROM") "TGaupp")
      )
      (libsource (lib "user") (part "Resistor"))
    )
    (comp (ref "R126")
      (value "82k")
      (footprint "RES 1206_3216")
      (description "SMD resistor 82Kohms .1% 25ppm")
      (fields
        (field (name "MANUFACTURER") "Vishay")
        (field (name "MANUFACTURER PART NUMBER") "TNPW120682K0BEEA")
        (field (name "CREATED FROM") "TGaupp")
      )
      (libsource (lib "user") (part "Resistor"))
    )
    (comp (ref "R127")
      (value "82k")
      (footprint "RES 1206_3216")
      (description "SMD resistor 82Kohms .1% 25ppm")
      (fields
        (field (name "MANUFACTURER") "Vishay")
        (field (name "MANUFACTURER PART NUMBER") "TNPW120682K0BEEA")
        (field (name "CREATED FROM") "TGaupp")
      )
      (libsource (lib "user") (part "Resistor"))
    )
    (comp (ref "R128")
      (value "82k")
      (footprint "RES 1206_3216")
      (description "SMD resistor 82Kohms .1% 25ppm")
      (fields
        (field (name "MANUFACTURER") "Vishay")
        (field (name "MANUFACTURER PART NUMBER") "TNPW120682K0BEEA")
        (field (name "CREATED FROM") "TGaupp")
      )
      (libsource (lib "user") (part "Resistor"))
    )
    (comp (ref "R129")
      (value "82k")
      (footprint "RES 1206_3216")
      (description "SMD resistor 82Kohms .1% 25ppm")
      (fields
        (field (name "MANUFACTURER") "Vishay")
        (field (name "MANUFACTURER PART NUMBER") "TNPW120682K0BEEA")
        (field (name "CREATED FROM") "TGaupp")
      )
      (libsource (lib "user") (part "Resistor"))
    )
    (comp (ref "R130")
      (value "82k")
      (footprint "RES 1206_3216")
      (description "SMD resistor 82Kohms .1% 25ppm")
      (fields
        (field (name "MANUFACTURER") "Vishay")
        (field (name "MANUFACTURER PART NUMBER") "TNPW120682K0BEEA")
        (field (name "CREATED FROM") "TGaupp")
      )
      (libsource (lib "user") (part "Resistor"))
    )
    (comp (ref "R131")
      (value "82k")
      (footprint "RES 1206_3216")
      (description "SMD resistor 82Kohms .1% 25ppm")
      (fields
        (field (name "MANUFACTURER") "Vishay")
        (field (name "MANUFACTURER PART NUMBER") "TNPW120682K0BEEA")
        (field (name "CREATED FROM") "TGaupp")
      )
      (libsource (lib "user") (part "Resistor"))
    )
    (comp (ref "R132")
      (value "82k")
      (footprint "RES 1206_3216")
      (description "SMD resistor 82Kohms .1% 25ppm")
      (fields
        (field (name "MANUFACTURER") "Vishay")
        (field (name "MANUFACTURER PART NUMBER") "TNPW120682K0BEEA")
        (field (name "CREATED FROM") "TGaupp")
      )
      (libsource (lib "user") (part "Resistor"))
    )
    (comp (ref "R133")
      (value "82k")
      (footprint "RES 1206_3216")
      (description "SMD resistor 82Kohms .1% 25ppm")
      (fields
        (field (name "MANUFACTURER") "Vishay")
        (field (name "MANUFACTURER PART NUMBER") "TNPW120682K0BEEA")
        (field (name "CREATED FROM") "TGaupp")
      )
      (libsource (lib "user") (part "Resistor"))
    )
    (comp (ref "R134")
      (value "82k")
      (footprint "RES 1206_3216")
      (description "SMD resistor 82Kohms .1% 25ppm")
      (fields
        (field (name "MANUFACTURER") "Vishay")
        (field (name "MANUFACTURER PART NUMBER") "TNPW120682K0BEEA")
        (field (name "CREATED FROM") "TGaupp")
      )
      (libsource (lib "user") (part "Resistor"))
    )
    (comp (ref "R135")
      (value "82k")
      (footprint "RES 1206_3216")
      (description "SMD resistor 82Kohms .1% 25ppm")
      (fields
        (field (name "MANUFACTURER") "Vishay")
        (field (name "MANUFACTURER PART NUMBER") "TNPW120682K0BEEA")
        (field (name "CREATED FROM") "TGaupp")
      )
      (libsource (lib "user") (part "Resistor"))
    )
    (comp (ref "R136")
      (value "82k")
      (footprint "RES 1206_3216")
      (description "SMD resistor 82Kohms .1% 25ppm")
      (fields
        (field (name "MANUFACTURER") "Vishay")
        (field (name "MANUFACTURER PART NUMBER") "TNPW120682K0BEEA")
        (field (name "CREATED FROM") "TGaupp")
      )
      (libsource (lib "user") (part "Resistor"))
    )
    (comp (ref "R137")
      (value "82k")
      (footprint "RES 1206_3216")
      (description "SMD resistor 82Kohms .1% 25ppm")
      (fields
        (field (name "MANUFACTURER") "Vishay")
        (field (name "MANUFACTURER PART NUMBER") "TNPW120682K0BEEA")
        (field (name "CREATED FROM") "TGaupp")
      )
      (libsource (lib "user") (part "Resistor"))
    )
    (comp (ref "R138")
      (value "82k")
      (footprint "RES 1206_3216")
      (description "SMD resistor 82Kohms .1% 25ppm")
      (fields
        (field (name "MANUFACTURER") "Vishay")
        (field (name "MANUFACTURER PART NUMBER") "TNPW120682K0BEEA")
        (field (name "CREATED FROM") "TGaupp")
      )
      (libsource (lib "user") (part "Resistor"))
    )
    (comp (ref "R139")
      (value "82k")
      (footprint "RES 1206_3216")
      (description "SMD resistor 82Kohms .1% 25ppm")
      (fields
        (field (name "MANUFACTURER") "Vishay")
        (field (name "MANUFACTURER PART NUMBER") "TNPW120682K0BEEA")
        (field (name "CREATED FROM") "TGaupp")
      )
      (libsource (lib "user") (part "Resistor"))
    )
    (comp (ref "R140")
      (value "82k")
      (footprint "RES 1206_3216")
      (description "SMD resistor 82Kohms .1% 25ppm")
      (fields
        (field (name "MANUFACTURER") "Vishay")
        (field (name "MANUFACTURER PART NUMBER") "TNPW120682K0BEEA")
        (field (name "CREATED FROM") "TGaupp")
      )
      (libsource (lib "user") (part "Resistor"))
    )
    (comp (ref "R141")
      (value "82k")
      (footprint "RES 1206_3216")
      (description "SMD resistor 82Kohms .1% 25ppm")
      (fields
        (field (name "MANUFACTURER") "Vishay")
        (field (name "MANUFACTURER PART NUMBER") "TNPW120682K0BEEA")
        (field (name "CREATED FROM") "TGaupp")
      )
      (libsource (lib "user") (part "Resistor"))
    )
    (comp (ref "R142")
      (value "82k")
      (footprint "RES 1206_3216")
      (description "SMD resistor 82Kohms .1% 25ppm")
      (fields
        (field (name "MANUFACTURER") "Vishay")
        (field (name "MANUFACTURER PART NUMBER") "TNPW120682K0BEEA")
        (field (name "CREATED FROM") "TGaupp")
      )
      (libsource (lib "user") (part "Resistor"))
    )
    (comp (ref "R143")
      (value "82k")
      (footprint "RES 1206_3216")
      (description "SMD resistor 82Kohms .1% 25ppm")
      (fields
        (field (name "MANUFACTURER") "Vishay")
        (field (name "MANUFACTURER PART NUMBER") "TNPW120682K0BEEA")
        (field (name "CREATED FROM") "TGaupp")
      )
      (libsource (lib "user") (part "Resistor"))
    )
    (comp (ref "R144")
      (value "82k")
      (footprint "RES 1206_3216")
      (description "SMD resistor 82Kohms .1% 25ppm")
      (fields
        (field (name "MANUFACTURER") "Vishay")
        (field (name "MANUFACTURER PART NUMBER") "TNPW120682K0BEEA")
        (field (name "CREATED FROM") "TGaupp")
      )
      (libsource (lib "user") (part "Resistor"))
    )
    (comp (ref "R145")
      (value "82k")
      (footprint "RES 1206_3216")
      (description "SMD resistor 82Kohms .1% 25ppm")
      (fields
        (field (name "MANUFACTURER") "Vishay")
        (field (name "MANUFACTURER PART NUMBER") "TNPW120682K0BEEA")
        (field (name "CREATED FROM") "TGaupp")
      )
      (libsource (lib "user") (part "Resistor"))
    )
    (comp (ref "R146")
      (value "82k")
      (footprint "RES 1206_3216")
      (description "SMD resistor 82Kohms .1% 25ppm")
      (fields
        (field (name "MANUFACTURER") "Vishay")
        (field (name "MANUFACTURER PART NUMBER") "TNPW120682K0BEEA")
        (field (name "CREATED FROM") "TGaupp")
      )
      (libsource (lib "user") (part "Resistor"))
    )
    (comp (ref "R147")
      (value "82k")
      (footprint "RES 1206_3216")
      (description "SMD resistor 82Kohms .1% 25ppm")
      (fields
        (field (name "MANUFACTURER") "Vishay")
        (field (name "MANUFACTURER PART NUMBER") "TNPW120682K0BEEA")
        (field (name "CREATED FROM") "TGaupp")
      )
      (libsource (lib "user") (part "Resistor"))
    )
    (comp (ref "R148")
      (value "82k")
      (footprint "RES 1206_3216")
      (description "SMD resistor 82Kohms .1% 25ppm")
      (fields
        (field (name "MANUFACTURER") "Vishay")
        (field (name "MANUFACTURER PART NUMBER") "TNPW120682K0BEEA")
        (field (name "CREATED FROM") "TGaupp")
      )
      (libsource (lib "user") (part "Resistor"))
    )
    (comp (ref "R149")
      (value "82k")
      (footprint "RES 1206_3216")
      (description "SMD resistor 82Kohms .1% 25ppm")
      (fields
        (field (name "MANUFACTURER") "Vishay")
        (field (name "MANUFACTURER PART NUMBER") "TNPW120682K0BEEA")
        (field (name "CREATED FROM") "TGaupp")
      )
      (libsource (lib "user") (part "Resistor"))
    )
    (comp (ref "R150")
      (value "82k")
      (footprint "RES 1206_3216")
      (description "SMD resistor 82Kohms .1% 25ppm")
      (fields
        (field (name "MANUFACTURER") "Vishay")
        (field (name "MANUFACTURER PART NUMBER") "TNPW120682K0BEEA")
        (field (name "CREATED FROM") "TGaupp")
      )
      (libsource (lib "user") (part "Resistor"))
    )
    (comp (ref "R151")
      (value "82k")
      (footprint "RES 1206_3216")
      (description "SMD resistor 82Kohms .1% 25ppm")
      (fields
        (field (name "MANUFACTURER") "Vishay")
        (field (name "MANUFACTURER PART NUMBER") "TNPW120682K0BEEA")
        (field (name "CREATED FROM") "TGaupp")
      )
      (libsource (lib "user") (part "Resistor"))
    )
    (comp (ref "R152")
      (value "82k")
      (footprint "RES 1206_3216")
      (description "SMD resistor 82Kohms .1% 25ppm")
      (fields
        (field (name "MANUFACTURER") "Vishay")
        (field (name "MANUFACTURER PART NUMBER") "TNPW120682K0BEEA")
        (field (name "CREATED FROM") "TGaupp")
      )
      (libsource (lib "user") (part "Resistor"))
    )
    (comp (ref "R153")
      (value "82k")
      (footprint "RES 1206_3216")
      (description "SMD resistor 82Kohms .1% 25ppm")
      (fields
        (field (name "MANUFACTURER") "Vishay")
        (field (name "MANUFACTURER PART NUMBER") "TNPW120682K0BEEA")
        (field (name "CREATED FROM") "TGaupp")
      )
      (libsource (lib "user") (part "Resistor"))
    )
    (comp (ref "R154")
      (value "82k")
      (footprint "RES 1206_3216")
      (description "SMD resistor 82Kohms .1% 25ppm")
      (fields
        (field (name "MANUFACTURER") "Vishay")
        (field (name "MANUFACTURER PART NUMBER") "TNPW120682K0BEEA")
        (field (name "CREATED FROM") "TGaupp")
      )
      (libsource (lib "user") (part "Resistor"))
    )
    (comp (ref "R155")
      (value "82k")
      (footprint "RES 1206_3216")
      (description "SMD resistor 82Kohms .1% 25ppm")
      (fields
        (field (name "MANUFACTURER") "Vishay")
        (field (name "MANUFACTURER PART NUMBER") "TNPW120682K0BEEA")
        (field (name "CREATED FROM") "TGaupp")
      )
      (libsource (lib "user") (part "Resistor"))
    )
    (comp (ref "R156")
      (value "82k")
      (footprint "RES 1206_3216")
      (description "SMD resistor 82Kohms .1% 25ppm")
      (fields
        (field (name "MANUFACTURER") "Vishay")
        (field (name "MANUFACTURER PART NUMBER") "TNPW120682K0BEEA")
        (field (name "CREATED FROM") "TGaupp")
      )
      (libsource (lib "user") (part "Resistor"))
    )
    (comp (ref "R157")
      (value "82k")
      (footprint "RES 1206_3216")
      (description "SMD resistor 82Kohms .1% 25ppm")
      (fields
        (field (name "MANUFACTURER") "Vishay")
        (field (name "MANUFACTURER PART NUMBER") "TNPW120682K0BEEA")
        (field (name "CREATED FROM") "TGaupp")
      )
      (libsource (lib "user") (part "Resistor"))
    )
    (comp (ref "R158")
      (value "82k")
      (footprint "RES 1206_3216")
      (description "SMD resistor 82Kohms .1% 25ppm")
      (fields
        (field (name "MANUFACTURER") "Vishay")
        (field (name "MANUFACTURER PART NUMBER") "TNPW120682K0BEEA")
        (field (name "CREATED FROM") "TGaupp")
      )
      (libsource (lib "user") (part "Resistor"))
    )
    (comp (ref "R159")
      (value "10R")
      (footprint "RES 0603_1608")
      (description "SMD 1/10watt 10ohms 1%")
      (fields
        (field (name "MANUFACTURER PART NUMBER") "CRCW060310R0FKTA")
        (field (name "MANUFACTURER") "Vishay")
        (field (name "CREATED FROM") "TGaupp")
      )
      (libsource (lib "user") (part "Resistor"))
    )
    (comp (ref "R160")
      (value "82R")
      (footprint "RES 1206_3216")
      (description "SMD resistor 1/4W 82 ohm .1% 25ppm")
      (fields
        (field (name "MANUFACTURER") "YAGEO")
        (field (name "MANUFACTURER PART NUMBER") "RT1206BRD0782RL")
        (field (name "CREATED FROM") "TGaupp")
      )
      (libsource (lib "user") (part "Resistor"))
    )
  )
  (nets
    (net (code "1") (name "/U_IN_N") (class "Default")
      (node (ref "C90") (pin "1") (pinfunction "1_1") (pintype "passive"))
      (node (ref "R78") (pin "1") (pinfunction "1_1") (pintype "passive"))
    )
    (net (code "2") (name "/U_Zwischen_N") (class "Default")
      (node (ref "C7") (pin "2") (pinfunction "2_2") (pintype "passive"))
      (node (ref "R159") (pin "2") (pinfunction "2_2") (pintype "passive"))
    )
    (net (code "3") (name "GND_HV") (class "Default")
      (node (ref "C173") (pin "1") (pinfunction "1_1") (pintype "passive"))
      (node (ref "C7") (pin "1") (pinfunction "1_1") (pintype "passive"))
      (node (ref "R160") (pin "1") (pinfunction "1_1") (pintype "passive"))
    )
    (net (code "4") (name "Net-(C90-Pad2)") (class "Default")
      (node (ref "C90") (pin "2") (pinfunction "2_2") (pintype "passive"))
      (node (ref "C91") (pin "1") (pinfunction "1_1") (pintype "passive"))
      (node (ref "R78") (pin "2") (pinfunction "2_2") (pintype "passive"))
      (node (ref "R79") (pin "1") (pinfunction "1_1") (pintype "passive"))
    )
    (net (code "5") (name "Net-(C91-Pad2)") (class "Default")
      (node (ref "C91") (pin "2") (pinfunction "2_2") (pintype "passive"))
      (node (ref "C92") (pin "1") (pinfunction "1_1") (pintype "passive"))
      (node (ref "R79") (pin "2") (pinfunction "2_2") (pintype "passive"))
      (node (ref "R80") (pin "1") (pinfunction "1_1") (pintype "passive"))
    )
    (net (code "6") (name "Net-(C92-Pad2)") (class "Default")
      (node (ref "C92") (pin "2") (pinfunction "2_2") (pintype "passive"))
      (node (ref "C93") (pin "1") (pinfunction "1_1") (pintype "passive"))
      (node (ref "R80") (pin "2") (pinfunction "2_2") (pintype "passive"))
      (node (ref "R81") (pin "1") (pinfunction "1_1") (pintype "passive"))
    )
    (net (code "7") (name "Net-(C93-Pad2)") (class "Default")
      (node (ref "C93") (pin "2") (pinfunction "2_2") (pintype "passive"))
      (node (ref "C94") (pin "1") (pinfunction "1_1") (pintype "passive"))
      (node (ref "R81") (pin "2") (pinfunction "2_2") (pintype "passive"))
      (node (ref "R82") (pin "1") (pinfunction "1_1") (pintype "passive"))
    )
    (net (code "8") (name "Net-(C94-Pad2)") (class "Default")
      (node (ref "C94") (pin "2") (pinfunction "2_2") (pintype "passive"))
      (node (ref "C95") (pin "1") (pinfunction "1_1") (pintype "passive"))
      (node (ref "R82") (pin "2") (pinfunction "2_2") (pintype "passive"))
      (node (ref "R83") (pin "1") (pinfunction "1_1") (pintype "passive"))
    )
    (net (code "9") (name "Net-(C95-Pad2)") (class "Default")
      (node (ref "C95") (pin "2") (pinfunction "2_2") (pintype "passive"))
      (node (ref "C96") (pin "1") (pinfunction "1_1") (pintype "passive"))
      (node (ref "R83") (pin "2") (pinfunction "2_2") (pintype "passive"))
      (node (ref "R84") (pin "1") (pinfunction "1_1") (pintype "passive"))
    )
    (net (code "10") (name "Net-(C103-Pad1)") (class "Default")
      (node (ref "C103") (pin "1") (pinfunction "1_1") (pintype "passive"))
      (node (ref "C96") (pin "2") (pinfunction "2_2") (pintype "passive"))
      (node (ref "R84") (pin "2") (pinfunction "2_2") (pintype "passive"))
      (node (ref "R91") (pin "1") (pinfunction "1_1") (pintype "passive"))
    )
    (net (code "11") (name "Net-(C103-Pad2)") (class "Default")
      (node (ref "C103") (pin "2") (pinfunction "2_2") (pintype "passive"))
      (node (ref "C106") (pin "1") (pinfunction "1_1") (pintype "passive"))
      (node (ref "R91") (pin "2") (pinfunction "2_2") (pintype "passive"))
      (node (ref "R92") (pin "1") (pinfunction "1_1") (pintype "passive"))
    )
    (net (code "12") (name "Net-(C106-Pad2)") (class "Default")
      (node (ref "C106") (pin "2") (pinfunction "2_2") (pintype "passive"))
      (node (ref "C107") (pin "1") (pinfunction "1_1") (pintype "passive"))
      (node (ref "R92") (pin "2") (pinfunction "2_2") (pintype "passive"))
      (node (ref "R93") (pin "1") (pinfunction "1_1") (pintype "passive"))
    )
    (net (code "13") (name "Net-(C107-Pad2)") (class "Default")
      (node (ref "C107") (pin "2") (pinfunction "2_2") (pintype "passive"))
      (node (ref "C108") (pin "1") (pinfunction "1_1") (pintype "passive"))
      (node (ref "R93") (pin "2") (pinfunction "2_2") (pintype "passive"))
      (node (ref "R94") (pin "1") (pinfunction "1_1") (pintype "passive"))
    )
    (net (code "14") (name "Net-(C108-Pad2)") (class "Default")
      (node (ref "C108") (pin "2") (pinfunction "2_2") (pintype "passive"))
      (node (ref "C109") (pin "1") (pinfunction "1_1") (pintype "passive"))
      (node (ref "R94") (pin "2") (pinfunction "2_2") (pintype "passive"))
      (node (ref "R95") (pin "1") (pinfunction "1_1") (pintype "passive"))
    )
    (net (code "15") (name "Net-(C109-Pad2)") (class "Default")
      (node (ref "C109") (pin "2") (pinfunction "2_2") (pintype "passive"))
      (node (ref "C110") (pin "1") (pinfunction "1_1") (pintype "passive"))
      (node (ref "R95") (pin "2") (pinfunction "2_2") (pintype "passive"))
      (node (ref "R96") (pin "1") (pinfunction "1_1") (pintype "passive"))
    )
    (net (code "16") (name "Net-(C110-Pad2)") (class "Default")
      (node (ref "C110") (pin "2") (pinfunction "2_2") (pintype "passive"))
      (node (ref "C111") (pin "1") (pinfunction "1_1") (pintype "passive"))
      (node (ref "R96") (pin "2") (pinfunction "2_2") (pintype "passive"))
      (node (ref "R97") (pin "1") (pinfunction "1_1") (pintype "passive"))
    )
    (net (code "17") (name "Net-(C111-Pad2)") (class "Default")
      (node (ref "C111") (pin "2") (pinfunction "2_2") (pintype "passive"))
      (node (ref "C112") (pin "1") (pinfunction "1_1") (pintype "passive"))
      (node (ref "R97") (pin "2") (pinfunction "2_2") (pintype "passive"))
      (node (ref "R98") (pin "1") (pinfunction "1_1") (pintype "passive"))
    )
    (net (code "18") (name "Net-(C112-Pad2)") (class "Default")
      (node (ref "C112") (pin "2") (pinfunction "2_2") (pintype "passive"))
      (node (ref "C113") (pin "1") (pinfunction "1_1") (pintype "passive"))
      (node (ref "R98") (pin "2") (pinfunction "2_2") (pintype "passive"))
      (node (ref "R99") (pin "1") (pinfunction "1_1") (pintype "passive"))
    )
    (net (code "19") (name "Net-(C113-Pad2)") (class "Default")
      (node (ref "C113") (pin "2") (pinfunction "2_2") (pintype "passive"))
      (node (ref "C114") (pin "1") (pinfunction "1_1") (pintype "passive"))
      (node (ref "R100") (pin "1") (pinfunction "1_1") (pintype "passive"))
      (node (ref "R99") (pin "2") (pinfunction "2_2") (pintype "passive"))
    )
    (net (code "20") (name "Net-(C114-Pad2)") (class "Default")
      (node (ref "C114") (pin "2") (pinfunction "2_2") (pintype "passive"))
      (node (ref "C115") (pin "1") (pinfunction "1_1") (pintype "passive"))
      (node (ref "R100") (pin "2") (pinfunction "2_2") (pintype "passive"))
      (node (ref "R101") (pin "1") (pinfunction "1_1") (pintype "passive"))
    )
    (net (code "21") (name "Net-(C115-Pad2)") (class "Default")
      (node (ref "C115") (pin "2") (pinfunction "2_2") (pintype "passive"))
      (node (ref "C116") (pin "1") (pinfunction "1_1") (pintype "passive"))
      (node (ref "R101") (pin "2") (pinfunction "2_2") (pintype "passive"))
      (node (ref "R102") (pin "1") (pinfunction "1_1") (pintype "passive"))
    )
    (net (code "22") (name "Net-(C116-Pad2)") (class "Default")
      (node (ref "C116") (pin "2") (pinfunction "2_2") (pintype "passive"))
      (node (ref "C117") (pin "1") (pinfunction "1_1") (pintype "passive"))
      (node (ref "R102") (pin "2") (pinfunction "2_2") (pintype "passive"))
      (node (ref "R103") (pin "1") (pinfunction "1_1") (pintype "passive"))
    )
    (net (code "23") (name "Net-(C117-Pad2)") (class "Default")
      (node (ref "C117") (pin "2") (pinfunction "2_2") (pintype "passive"))
      (node (ref "C118") (pin "1") (pinfunction "1_1") (pintype "passive"))
      (node (ref "R103") (pin "2") (pinfunction "2_2") (pintype "passive"))
      (node (ref "R104") (pin "1") (pinfunction "1_1") (pintype "passive"))
    )
    (net (code "24") (name "Net-(C118-Pad2)") (class "Default")
      (node (ref "C118") (pin "2") (pinfunction "2_2") (pintype "passive"))
      (node (ref "C119") (pin "1") (pinfunction "1_1") (pintype "passive"))
      (node (ref "R104") (pin "2") (pinfunction "2_2") (pintype "passive"))
      (node (ref "R105") (pin "1") (pinfunction "1_1") (pintype "passive"))
    )
    (net (code "25") (name "Net-(C119-Pad2)") (class "Default")
      (node (ref "C119") (pin "2") (pinfunction "2_2") (pintype "passive"))
      (node (ref "C120") (pin "1") (pinfunction "1_1") (pintype "passive"))
      (node (ref "R105") (pin "2") (pinfunction "2_2") (pintype "passive"))
      (node (ref "R106") (pin "1") (pinfunction "1_1") (pintype "passive"))
    )
    (net (code "26") (name "Net-(C120-Pad2)") (class "Default")
      (node (ref "C120") (pin "2") (pinfunction "2_2") (pintype "passive"))
      (node (ref "C121") (pin "1") (pinfunction "1_1") (pintype "passive"))
      (node (ref "R106") (pin "2") (pinfunction "2_2") (pintype "passive"))
      (node (ref "R107") (pin "1") (pinfunction "1_1") (pintype "passive"))
    )
    (net (code "27") (name "Net-(C121-Pad2)") (class "Default")
      (node (ref "C121") (pin "2") (pinfunction "2_2") (pintype "passive"))
      (node (ref "C122") (pin "1") (pinfunction "1_1") (pintype "passive"))
      (node (ref "R107") (pin "2") (pinfunction "2_2") (pintype "passive"))
      (node (ref "R108") (pin "1") (pinfunction "1_1") (pintype "passive"))
    )
    (net (code "28") (name "Net-(C122-Pad2)") (class "Default")
      (node (ref "C122") (pin "2") (pinfunction "2_2") (pintype "passive"))
      (node (ref "C123") (pin "1") (pinfunction "1_1") (pintype "passive"))
      (node (ref "R108") (pin "2") (pinfunction "2_2") (pintype "passive"))
      (node (ref "R109") (pin "1") (pinfunction "1_1") (pintype "passive"))
    )
    (net (code "29") (name "Net-(C123-Pad2)") (class "Default")
      (node (ref "C123") (pin "2") (pinfunction "2_2") (pintype "passive"))
      (node (ref "C124") (pin "1") (pinfunction "1_1") (pintype "passive"))
      (node (ref "R109") (pin "2") (pinfunction "2_2") (pintype "passive"))
      (node (ref "R110") (pin "1") (pinfunction "1_1") (pintype "passive"))
    )
    (net (code "30") (name "Net-(C124-Pad2)") (class "Default")
      (node (ref "C124") (pin "2") (pinfunction "2_2") (pintype "passive"))
      (node (ref "C125") (pin "1") (pinfunction "1_1") (pintype "passive"))
      (node (ref "R110") (pin "2") (pinfunction "2_2") (pintype "passive"))
      (node (ref "R111") (pin "1") (pinfunction "1_1") (pintype "passive"))
    )
    (net (code "31") (name "Net-(C125-Pad2)") (class "Default")
      (node (ref "C125") (pin "2") (pinfunction "2_2") (pintype "passive"))
      (node (ref "C126") (pin "1") (pinfunction "1_1") (pintype "passive"))
      (node (ref "R111") (pin "2") (pinfunction "2_2") (pintype "passive"))
      (node (ref "R112") (pin "1") (pinfunction "1_1") (pintype "passive"))
    )
    (net (code "32") (name "Net-(C126-Pad2)") (class "Default")
      (node (ref "C126") (pin "2") (pinfunction "2_2") (pintype "passive"))
      (node (ref "C127") (pin "1") (pinfunction "1_1") (pintype "passive"))
      (node (ref "R112") (pin "2") (pinfunction "2_2") (pintype "passive"))
      (node (ref "R113") (pin "1") (pinfunction "1_1") (pintype "passive"))
    )
    (net (code "33") (name "Net-(C127-Pad2)") (class "Default")
      (node (ref "C127") (pin "2") (pinfunction "2_2") (pintype "passive"))
      (node (ref "C128") (pin "1") (pinfunction "1_1") (pintype "passive"))
      (node (ref "R113") (pin "2") (pinfunction "2_2") (pintype "passive"))
      (node (ref "R114") (pin "1") (pinfunction "1_1") (pintype "passive"))
    )
    (net (code "34") (name "Net-(C128-Pad2)") (class "Default")
      (node (ref "C128") (pin "2") (pinfunction "2_2") (pintype "passive"))
      (node (ref "C129") (pin "1") (pinfunction "1_1") (pintype "passive"))
      (node (ref "R114") (pin "2") (pinfunction "2_2") (pintype "passive"))
      (node (ref "R115") (pin "1") (pinfunction "1_1") (pintype "passive"))
    )
    (net (code "35") (name "Net-(C129-Pad2)") (class "Default")
      (node (ref "C129") (pin "2") (pinfunction "2_2") (pintype "passive"))
      (node (ref "C130") (pin "1") (pinfunction "1_1") (pintype "passive"))
      (node (ref "R115") (pin "2") (pinfunction "2_2") (pintype "passive"))
      (node (ref "R116") (pin "1") (pinfunction "1_1") (pintype "passive"))
    )
    (net (code "36") (name "Net-(C130-Pad2)") (class "Default")
      (node (ref "C130") (pin "2") (pinfunction "2_2") (pintype "passive"))
      (node (ref "C131") (pin "1") (pinfunction "1_1") (pintype "passive"))
      (node (ref "R116") (pin "2") (pinfunction "2_2") (pintype "passive"))
      (node (ref "R117") (pin "1") (pinfunction "1_1") (pintype "passive"))
    )
    (net (code "37") (name "Net-(C131-Pad2)") (class "Default")
      (node (ref "C131") (pin "2") (pinfunction "2_2") (pintype "passive"))
      (node (ref "C132") (pin "1") (pinfunction "1_1") (pintype "passive"))
      (node (ref "R117") (pin "2") (pinfunction "2_2") (pintype "passive"))
      (node (ref "R118") (pin "1") (pinfunction "1_1") (pintype "passive"))
    )
    (net (code "38") (name "Net-(C132-Pad2)") (class "Default")
      (node (ref "C132") (pin "2") (pinfunction "2_2") (pintype "passive"))
      (node (ref "C133") (pin "1") (pinfunction "1_1") (pintype "passive"))
      (node (ref "R118") (pin "2") (pinfunction "2_2") (pintype "passive"))
      (node (ref "R119") (pin "1") (pinfunction "1_1") (pintype "passive"))
    )
    (net (code "39") (name "Net-(C133-Pad2)") (class "Default")
      (node (ref "C133") (pin "2") (pinfunction "2_2") (pintype "passive"))
      (node (ref "C134") (pin "1") (pinfunction "1_1") (pintype "passive"))
      (node (ref "R119") (pin "2") (pinfunction "2_2") (pintype "passive"))
      (node (ref "R120") (pin "1") (pinfunction "1_1") (pintype "passive"))
    )
    (net (code "40") (name "Net-(C134-Pad2)") (class "Default")
      (node (ref "C134") (pin "2") (pinfunction "2_2") (pintype "passive"))
      (node (ref "C135") (pin "1") (pinfunction "1_1") (pintype "passive"))
      (node (ref "R120") (pin "2") (pinfunction "2_2") (pintype "passive"))
      (node (ref "R121") (pin "1") (pinfunction "1_1") (pintype "passive"))
    )
    (net (code "41") (name "Net-(C135-Pad2)") (class "Default")
      (node (ref "C135") (pin "2") (pinfunction "2_2") (pintype "passive"))
      (node (ref "C136") (pin "1") (pinfunction "1_1") (pintype "passive"))
      (node (ref "R121") (pin "2") (pinfunction "2_2") (pintype "passive"))
      (node (ref "R122") (pin "1") (pinfunction "1_1") (pintype "passive"))
    )
    (net (code "42") (name "Net-(C136-Pad2)") (class "Default")
      (node (ref "C136") (pin "2") (pinfunction "2_2") (pintype "passive"))
      (node (ref "C137") (pin "1") (pinfunction "1_1") (pintype "passive"))
      (node (ref "R122") (pin "2") (pinfunction "2_2") (pintype "passive"))
      (node (ref "R123") (pin "1") (pinfunction "1_1") (pintype "passive"))
    )
    (net (code "43") (name "Net-(C137-Pad2)") (class "Default")
      (node (ref "C137") (pin "2") (pinfunction "2_2") (pintype "passive"))
      (node (ref "C138") (pin "1") (pinfunction "1_1") (pintype "passive"))
      (node (ref "R123") (pin "2") (pinfunction "2_2") (pintype "passive"))
      (node (ref "R124") (pin "1") (pinfunction "1_1") (pintype "passive"))
    )
    (net (code "44") (name "Net-(C138-Pad2)") (class "Default")
      (node (ref "C138") (pin "2") (pinfunction "2_2") (pintype "passive"))
      (node (ref "C139") (pin "1") (pinfunction "1_1") (pintype "passive"))
      (node (ref "R124") (pin "2") (pinfunction "2_2") (pintype "passive"))
      (node (ref "R125") (pin "1") (pinfunction "1_1") (pintype "passive"))
    )
    (net (code "45") (name "Net-(C139-Pad2)") (class "Default")
      (node (ref "C139") (pin "2") (pinfunction "2_2") (pintype "passive"))
      (node (ref "C140") (pin "1") (pinfunction "1_1") (pintype "passive"))
      (node (ref "R125") (pin "2") (pinfunction "2_2") (pintype "passive"))
      (node (ref "R126") (pin "1") (pinfunction "1_1") (pintype "passive"))
    )
    (net (code "46") (name "Net-(C140-Pad2)") (class "Default")
      (node (ref "C140") (pin "2") (pinfunction "2_2") (pintype "passive"))
      (node (ref "C141") (pin "1") (pinfunction "1_1") (pintype "passive"))
      (node (ref "R126") (pin "2") (pinfunction "2_2") (pintype "passive"))
      (node (ref "R127") (pin "1") (pinfunction "1_1") (pintype "passive"))
    )
    (net (code "47") (name "Net-(C141-Pad2)") (class "Default")
      (node (ref "C141") (pin "2") (pinfunction "2_2") (pintype "passive"))
      (node (ref "C142") (pin "1") (pinfunction "1_1") (pintype "passive"))
      (node (ref "R127") (pin "2") (pinfunction "2_2") (pintype "passive"))
      (node (ref "R128") (pin "1") (pinfunction "1_1") (pintype "passive"))
    )
    (net (code "48") (name "Net-(C142-Pad2)") (class "Default")
      (node (ref "C142") (pin "2") (pinfunction "2_2") (pintype "passive"))
      (node (ref "C143") (pin "1") (pinfunction "1_1") (pintype "passive"))
      (node (ref "R128") (pin "2") (pinfunction "2_2") (pintype "passive"))
      (node (ref "R129") (pin "1") (pinfunction "1_1") (pintype "passive"))
    )
    (net (code "49") (name "Net-(C143-Pad2)") (class "Default")
      (node (ref "C143") (pin "2") (pinfunction "2_2") (pintype "passive"))
      (node (ref "C144") (pin "1") (pinfunction "1_1") (pintype "passive"))
      (node (ref "R129") (pin "2") (pinfunction "2_2") (pintype "passive"))
      (node (ref "R130") (pin "1") (pinfunction "1_1") (pintype "passive"))
    )
    (net (code "50") (name "Net-(C144-Pad2)") (class "Default")
      (node (ref "C144") (pin "2") (pinfunction "2_2") (pintype "passive"))
      (node (ref "C145") (pin "1") (pinfunction "1_1") (pintype "passive"))
      (node (ref "R130") (pin "2") (pinfunction "2_2") (pintype "passive"))
      (node (ref "R131") (pin "1") (pinfunction "1_1") (pintype "passive"))
    )
    (net (code "51") (name "Net-(C145-Pad2)") (class "Default")
      (node (ref "C145") (pin "2") (pinfunction "2_2") (pintype "passive"))
      (node (ref "C146") (pin "1") (pinfunction "1_1") (pintype "passive"))
      (node (ref "R131") (pin "2") (pinfunction "2_2") (pintype "passive"))
      (node (ref "R132") (pin "1") (pinfunction "1_1") (pintype "passive"))
    )
    (net (code "52") (name "Net-(C146-Pad2)") (class "Default")
      (node (ref "C146") (pin "2") (pinfunction "2_2") (pintype "passive"))
      (node (ref "C147") (pin "1") (pinfunction "1_1") (pintype "passive"))
      (node (ref "R132") (pin "2") (pinfunction "2_2") (pintype "passive"))
      (node (ref "R133") (pin "1") (pinfunction "1_1") (pintype "passive"))
    )
    (net (code "53") (name "Net-(C147-Pad2)") (class "Default")
      (node (ref "C147") (pin "2") (pinfunction "2_2") (pintype "passive"))
      (node (ref "C148") (pin "1") (pinfunction "1_1") (pintype "passive"))
      (node (ref "R133") (pin "2") (pinfunction "2_2") (pintype "passive"))
      (node (ref "R134") (pin "1") (pinfunction "1_1") (pintype "passive"))
    )
    (net (code "54") (name "Net-(C148-Pad2)") (class "Default")
      (node (ref "C148") (pin "2") (pinfunction "2_2") (pintype "passive"))
      (node (ref "C149") (pin "1") (pinfunction "1_1") (pintype "passive"))
      (node (ref "R134") (pin "2") (pinfunction "2_2") (pintype "passive"))
      (node (ref "R135") (pin "1") (pinfunction "1_1") (pintype "passive"))
    )
    (net (code "55") (name "Net-(C149-Pad2)") (class "Default")
      (node (ref "C149") (pin "2") (pinfunction "2_2") (pintype "passive"))
      (node (ref "C150") (pin "1") (pinfunction "1_1") (pintype "passive"))
      (node (ref "R135") (pin "2") (pinfunction "2_2") (pintype "passive"))
      (node (ref "R136") (pin "1") (pinfunction "1_1") (pintype "passive"))
    )
    (net (code "56") (name "Net-(C150-Pad2)") (class "Default")
      (node (ref "C150") (pin "2") (pinfunction "2_2") (pintype "passive"))
      (node (ref "C151") (pin "1") (pinfunction "1_1") (pintype "passive"))
      (node (ref "R136") (pin "2") (pinfunction "2_2") (pintype "passive"))
      (node (ref "R137") (pin "1") (pinfunction "1_1") (pintype "passive"))
    )
    (net (code "57") (name "Net-(C151-Pad2)") (class "Default")
      (node (ref "C151") (pin "2") (pinfunction "2_2") (pintype "passive"))
      (node (ref "C152") (pin "1") (pinfunction "1_1") (pintype "passive"))
      (node (ref "R137") (pin "2") (pinfunction "2_2") (pintype "passive"))
      (node (ref "R138") (pin "1") (pinfunction "1_1") (pintype "passive"))
    )
    (net (code "58") (name "Net-(C152-Pad2)") (class "Default")
      (node (ref "C152") (pin "2") (pinfunction "2_2") (pintype "passive"))
      (node (ref "C153") (pin "1") (pinfunction "1_1") (pintype "passive"))
      (node (ref "R138") (pin "2") (pinfunction "2_2") (pintype "passive"))
      (node (ref "R139") (pin "1") (pinfunction "1_1") (pintype "passive"))
    )
    (net (code "59") (name "Net-(C153-Pad2)") (class "Default")
      (node (ref "C153") (pin "2") (pinfunction "2_2") (pintype "passive"))
      (node (ref "C154") (pin "1") (pinfunction "1_1") (pintype "passive"))
      (node (ref "R139") (pin "2") (pinfunction "2_2") (pintype "passive"))
      (node (ref "R140") (pin "1") (pinfunction "1_1") (pintype "passive"))
    )
    (net (code "60") (name "Net-(C154-Pad2)") (class "Default")
      (node (ref "C154") (pin "2") (pinfunction "2_2") (pintype "passive"))
      (node (ref "C155") (pin "1") (pinfunction "1_1") (pintype "passive"))
      (node (ref "R140") (pin "2") (pinfunction "2_2") (pintype "passive"))
      (node (ref "R141") (pin "1") (pinfunction "1_1") (pintype "passive"))
    )
    (net (code "61") (name "Net-(C155-Pad2)") (class "Default")
      (node (ref "C155") (pin "2") (pinfunction "2_2") (pintype "passive"))
      (node (ref "C156") (pin "1") (pinfunction "1_1") (pintype "passive"))
      (node (ref "R141") (pin "2") (pinfunction "2_2") (pintype "passive"))
      (node (ref "R142") (pin "1") (pinfunction "1_1") (pintype "passive"))
    )
    (net (code "62") (name "Net-(C156-Pad2)") (class "Default")
      (node (ref "C156") (pin "2") (pinfunction "2_2") (pintype "passive"))
      (node (ref "C157") (pin "1") (pinfunction "1_1") (pintype "passive"))
      (node (ref "R142") (pin "2") (pinfunction "2_2") (pintype "passive"))
      (node (ref "R143") (pin "1") (pinfunction "1_1") (pintype "passive"))
    )
    (net (code "63") (name "Net-(C157-Pad2)") (class "Default")
      (node (ref "C157") (pin "2") (pinfunction "2_2") (pintype "passive"))
      (node (ref "C158") (pin "1") (pinfunction "1_1") (pintype "passive"))
      (node (ref "R143") (pin "2") (pinfunction "2_2") (pintype "passive"))
      (node (ref "R144") (pin "1") (pinfunction "1_1") (pintype "passive"))
    )
    (net (code "64") (name "Net-(C158-Pad2)") (class "Default")
      (node (ref "C158") (pin "2") (pinfunction "2_2") (pintype "passive"))
      (node (ref "C159") (pin "1") (pinfunction "1_1") (pintype "passive"))
      (node (ref "R144") (pin "2") (pinfunction "2_2") (pintype "passive"))
      (node (ref "R145") (pin "1") (pinfunction "1_1") (pintype "passive"))
    )
    (net (code "65") (name "Net-(C159-Pad2)") (class "Default")
      (node (ref "C159") (pin "2") (pinfunction "2_2") (pintype "passive"))
      (node (ref "C160") (pin "1") (pinfunction "1_1") (pintype "passive"))
      (node (ref "R145") (pin "2") (pinfunction "2_2") (pintype "passive"))
      (node (ref "R146") (pin "1") (pinfunction "1_1") (pintype "passive"))
    )
    (net (code "66") (name "Net-(C160-Pad2)") (class "Default")
      (node (ref "C160") (pin "2") (pinfunction "2_2") (pintype "passive"))
      (node (ref "C161") (pin "1") (pinfunction "1_1") (pintype "passive"))
      (node (ref "R146") (pin "2") (pinfunction "2_2") (pintype "passive"))
      (node (ref "R147") (pin "1") (pinfunction "1_1") (pintype "passive"))
    )
    (net (code "67") (name "Net-(C161-Pad2)") (class "Default")
      (node (ref "C161") (pin "2") (pinfunction "2_2") (pintype "passive"))
      (node (ref "C162") (pin "1") (pinfunction "1_1") (pintype "passive"))
      (node (ref "R147") (pin "2") (pinfunction "2_2") (pintype "passive"))
      (node (ref "R148") (pin "1") (pinfunction "1_1") (pintype "passive"))
    )
    (net (code "68") (name "Net-(C162-Pad2)") (class "Default")
      (node (ref "C162") (pin "2") (pinfunction "2_2") (pintype "passive"))
      (node (ref "C163") (pin "1") (pinfunction "1_1") (pintype "passive"))
      (node (ref "R148") (pin "2") (pinfunction "2_2") (pintype "passive"))
      (node (ref "R149") (pin "1") (pinfunction "1_1") (pintype "passive"))
    )
    (net (code "69") (name "Net-(C163-Pad2)") (class "Default")
      (node (ref "C163") (pin "2") (pinfunction "2_2") (pintype "passive"))
      (node (ref "C164") (pin "1") (pinfunction "1_1") (pintype "passive"))
      (node (ref "R149") (pin "2") (pinfunction "2_2") (pintype "passive"))
      (node (ref "R150") (pin "1") (pinfunction "1_1") (pintype "passive"))
    )
    (net (code "70") (name "Net-(C164-Pad2)") (class "Default")
      (node (ref "C164") (pin "2") (pinfunction "2_2") (pintype "passive"))
      (node (ref "C165") (pin "1") (pinfunction "1_1") (pintype "passive"))
      (node (ref "R150") (pin "2") (pinfunction "2_2") (pintype "passive"))
      (node (ref "R151") (pin "1") (pinfunction "1_1") (pintype "passive"))
    )
    (net (code "71") (name "Net-(C165-Pad2)") (class "Default")
      (node (ref "C165") (pin "2") (pinfunction "2_2") (pintype "passive"))
      (node (ref "C166") (pin "1") (pinfunction "1_1") (pintype "passive"))
      (node (ref "R151") (pin "2") (pinfunction "2_2") (pintype "passive"))
      (node (ref "R152") (pin "1") (pinfunction "1_1") (pintype "passive"))
    )
    (net (code "72") (name "Net-(C166-Pad2)") (class "Default")
      (node (ref "C166") (pin "2") (pinfunction "2_2") (pintype "passive"))
      (node (ref "C167") (pin "1") (pinfunction "1_1") (pintype "passive"))
      (node (ref "R152") (pin "2") (pinfunction "2_2") (pintype "passive"))
      (node (ref "R153") (pin "1") (pinfunction "1_1") (pintype "passive"))
    )
    (net (code "73") (name "Net-(C167-Pad2)") (class "Default")
      (node (ref "C167") (pin "2") (pinfunction "2_2") (pintype "passive"))
      (node (ref "C168") (pin "1") (pinfunction "1_1") (pintype "passive"))
      (node (ref "R153") (pin "2") (pinfunction "2_2") (pintype "passive"))
      (node (ref "R154") (pin "1") (pinfunction "1_1") (pintype "passive"))
    )
    (net (code "74") (name "Net-(C168-Pad2)") (class "Default")
      (node (ref "C168") (pin "2") (pinfunction "2_2") (pintype "passive"))
      (node (ref "C169") (pin "1") (pinfunction "1_1") (pintype "passive"))
      (node (ref "R154") (pin "2") (pinfunction "2_2") (pintype "passive"))
      (node (ref "R155") (pin "1") (pinfunction "1_1") (pintype "passive"))
    )
    (net (code "75") (name "Net-(C169-Pad2)") (class "Default")
      (node (ref "C169") (pin "2") (pinfunction "2_2") (pintype "passive"))
      (node (ref "C170") (pin "1") (pinfunction "1_1") (pintype "passive"))
      (node (ref "R155") (pin "2") (pinfunction "2_2") (pintype "passive"))
      (node (ref "R156") (pin "1") (pinfunction "1_1") (pintype "passive"))
    )
    (net (code "76") (name "Net-(C170-Pad2)") (class "Default")
      (node (ref "C170") (pin "2") (pinfunction "2_2") (pintype "passive"))
      (node (ref "C171") (pin "1") (pinfunction "1_1") (pintype "passive"))
      (node (ref "R156") (pin "2") (pinfunction "2_2") (pintype "passive"))
      (node (ref "R157") (pin "1") (pinfunction "1_1") (pintype "passive"))
    )
    (net (code "77") (name "Net-(C171-Pad2)") (class "Default")
      (node (ref "C171") (pin "2") (pinfunction "2_2") (pintype "passive"))
      (node (ref "C172") (pin "1") (pinfunction "1_1") (pintype "passive"))
      (node (ref "R157") (pin "2") (pinfunction "2_2") (pintype "passive"))
      (node (ref "R158") (pin "1") (pinfunction "1_1") (pintype "passive"))
    )
    (net (code "78") (name "Net-(C172-Pad2)") (class "Default")
      (node (ref "C172") (pin "2") (pinfunction "2_2") (pintype "passive"))
      (node (ref "C173") (pin "2") (pinfunction "2_2") (pintype "passive"))
      (node (ref "R158") (pin "2") (pinfunction "2_2") (pintype "passive"))
      (node (ref "R159") (pin "1") (pinfunction "1_1") (pintype "passive"))
      (node (ref "R160") (pin "2") (pinfunction "2_2") (pintype "passive"))
    )
  )
)
